# MyNixie_-_HC595.net
KiCad netlist of a schematic drawn in Altium Designer
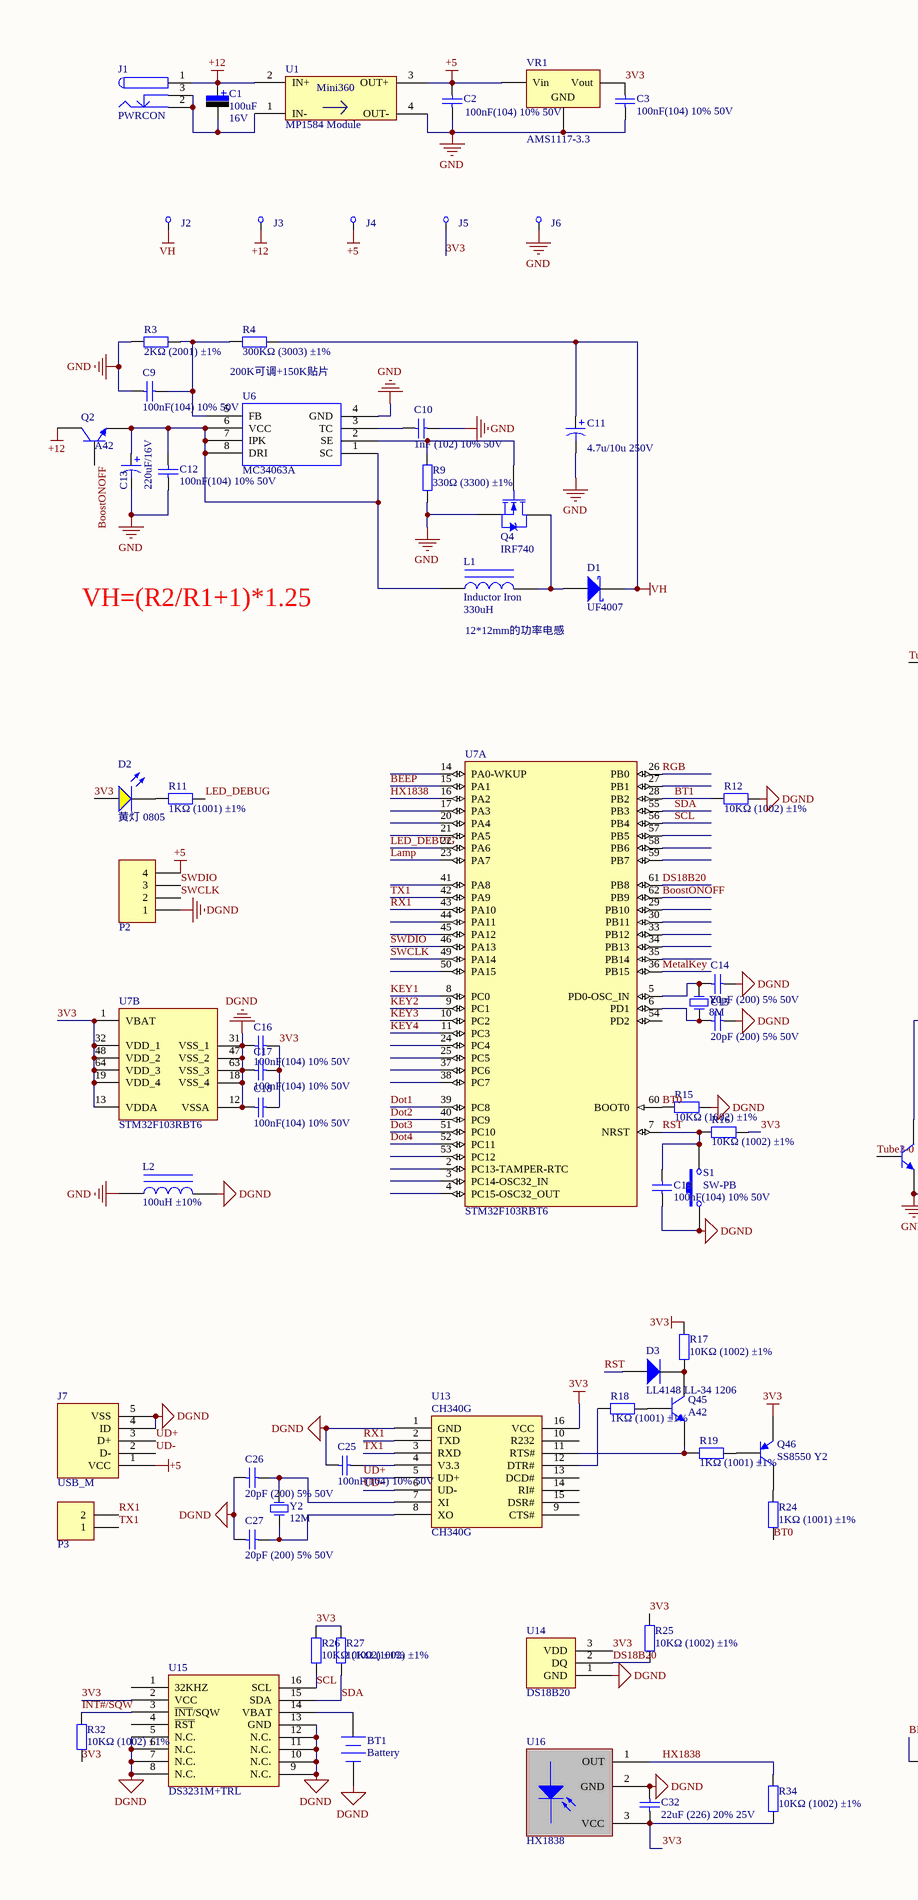
[diagram p0: MyNixie - HC595.SchDoc, left]
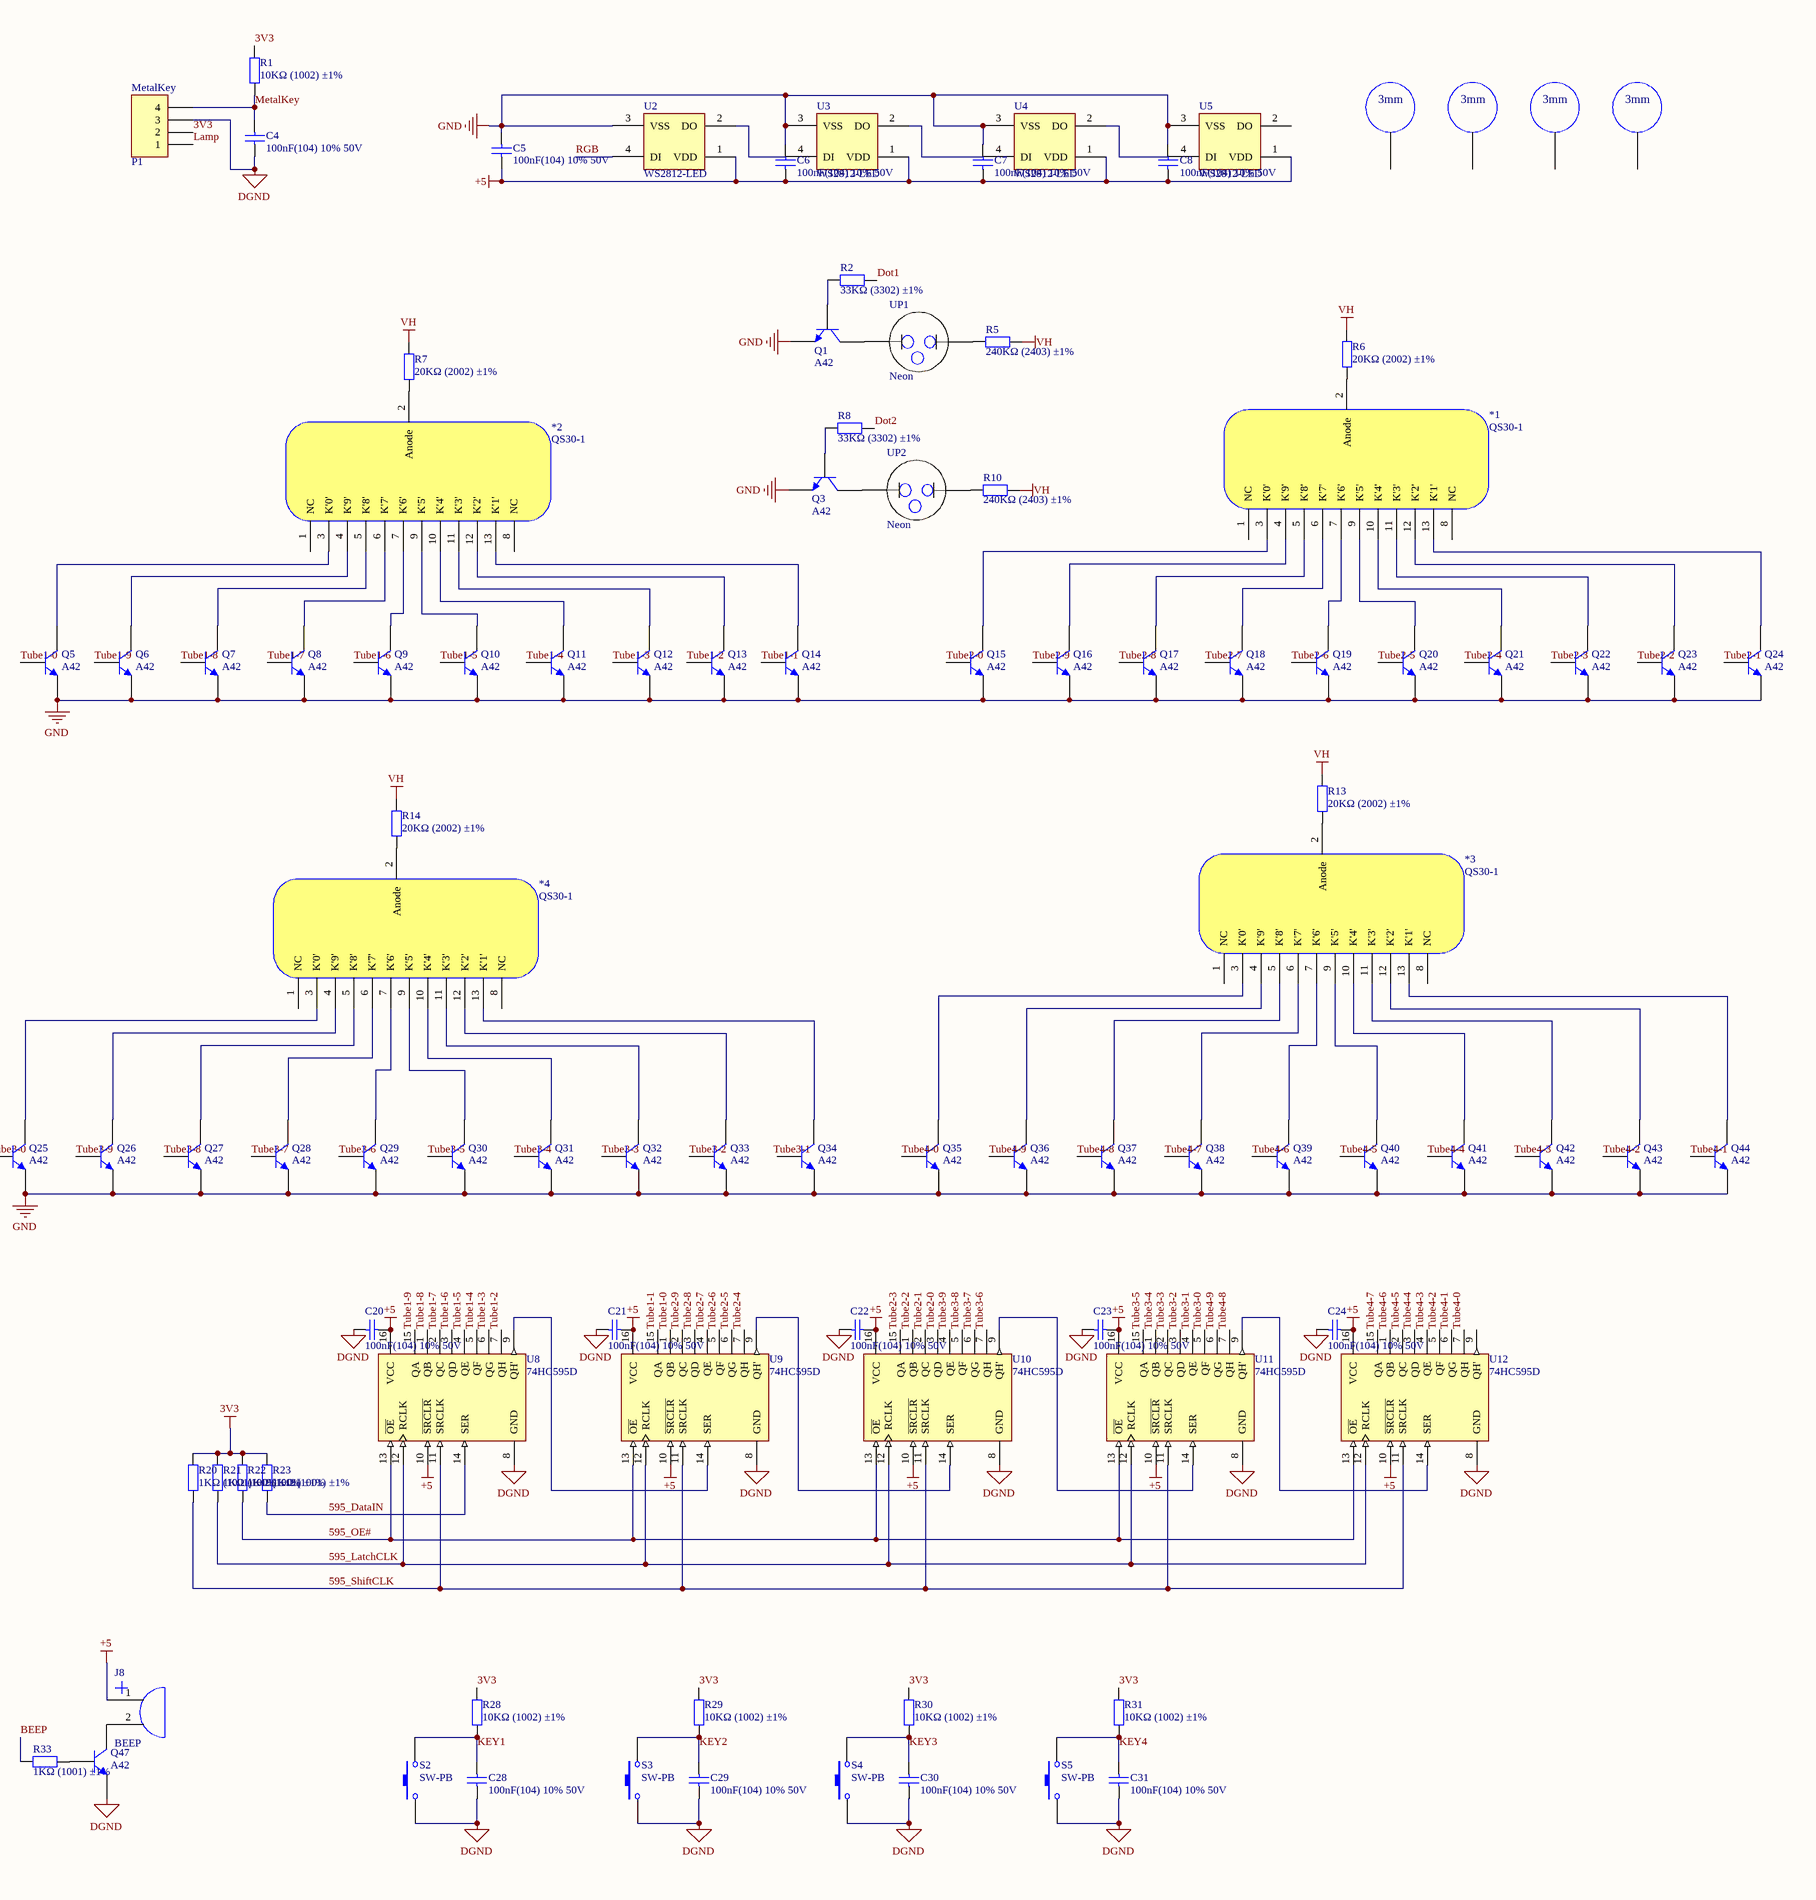
[diagram p1: MyNixie - HC595.SchDoc, right]

(export (version "E")
  (design (tool "Eeschema 10.0.6"))
  (components
    (comp (ref "*1")
      (value "QS30-1")
      (footprint "QS30-1")
      (description "南昌辉光管")
      (libsource (lib "fszhang") (part "QS30-1"))
    )
    (comp (ref "*2")
      (value "QS30-1")
      (footprint "QS30-1")
      (description "南昌辉光管")
      (libsource (lib "fszhang") (part "QS30-1"))
    )
    (comp (ref "*3")
      (value "QS30-1")
      (footprint "QS30-1")
      (description "南昌辉光管")
      (libsource (lib "fszhang") (part "QS30-1"))
    )
    (comp (ref "*4")
      (value "QS30-1")
      (footprint "QS30-1")
      (description "南昌辉光管")
      (libsource (lib "fszhang") (part "QS30-1"))
    )
    (comp (ref "BT1")
      (value "Battery")
      (footprint "CR1220")
      (description "备份电池")
      (fields (field (name "PUBLISHER") "Altium Limited"))
      (libsource (lib "fszhang") (part "Battery"))
    )
    (comp (ref "C1")
      (value "100uF")
      (footprint "C-RB-10")
      (description "极性电解电容")
      (fields
        (field (name "VOL") "16V")
        (field (name "Comment") "Cap Pol")
        (field (name "PUBLISHER") "Altium Limited")
      )
      (libsource (lib "fszhang") (part "Cap Pol"))
    )
    (comp (ref "C2")
      (value "100nF(104) 10% 50V")
      (footprint "LC-0805_C")
      (description "贴片电容")
      (libsource (lib "Miscellaneous Devices LC") (part "0805 100nF(104) 10% 50V"))
    )
    (comp (ref "C3")
      (value "100nF(104) 10% 50V")
      (footprint "LC-0805_C")
      (description "贴片电容")
      (libsource (lib "Miscellaneous Devices LC") (part "0805 100nF(104) 10% 50V"))
    )
    (comp (ref "C4")
      (value "100nF(104) 10% 50V")
      (footprint "LC-0805_C")
      (description "贴片电容")
      (libsource (lib "Miscellaneous Devices LC") (part "0805 100nF(104) 10% 50V"))
    )
    (comp (ref "C5")
      (value "100nF(104) 10% 50V")
      (footprint "LC-0805_C")
      (description "贴片电容")
      (libsource (lib "Miscellaneous Devices LC") (part "0805 100nF(104) 10% 50V"))
    )
    (comp (ref "C6")
      (value "100nF(104) 10% 50V")
      (footprint "LC-0805_C")
      (description "贴片电容")
      (libsource (lib "Miscellaneous Devices LC") (part "0805 100nF(104) 10% 50V"))
    )
    (comp (ref "C7")
      (value "100nF(104) 10% 50V")
      (footprint "LC-0805_C")
      (description "贴片电容")
      (libsource (lib "Miscellaneous Devices LC") (part "0805 100nF(104) 10% 50V"))
    )
    (comp (ref "C8")
      (value "100nF(104) 10% 50V")
      (footprint "LC-0805_C")
      (description "贴片电容")
      (libsource (lib "Miscellaneous Devices LC") (part "0805 100nF(104) 10% 50V"))
    )
    (comp (ref "C9")
      (value "100nF(104) 10% 50V")
      (footprint "LC-0805_C")
      (description "贴片电容")
      (libsource (lib "Miscellaneous Devices LC") (part "0805 100nF(104) 10% 50V"))
    )
    (comp (ref "C10")
      (value "1nF (102) 10% 50V")
      (footprint "LC-0805_C")
      (description "贴片电容")
      (libsource (lib "Miscellaneous Devices LC") (part "0805 1nF (102) 10% 50V"))
    )
    (comp (ref "C11")
      (value "4.7u/10u 250V")
      (footprint "C-RB-10")
      (description "Polarized Capacitor (Radial)")
      (fields (field (name "Comment") "Cap Pol1") (field (name "PUBLISHER") "Altium Limited"))
      (libsource (lib "Miscellaneous Devices") (part "Cap Pol1"))
    )
    (comp (ref "C12")
      (value "100nF(104) 10% 50V")
      (footprint "LC-0805_C")
      (description "贴片电容")
      (libsource (lib "Miscellaneous Devices LC") (part "0805 100nF(104) 10% 50V"))
    )
    (comp (ref "C13")
      (value "220uF/16V")
      (footprint "C-RB-6")
      (description "Polarized Capacitor (Radial)")
      (fields (field (name "Comment") "Cap Pol1") (field (name "PUBLISHER") "Altium Limited"))
      (libsource (lib "Miscellaneous Devices") (part "Cap Pol1"))
    )
    (comp (ref "C14")
      (value "20pF (200) 5% 50V")
      (footprint "LC-0805_C")
      (description "贴片电容")
      (libsource (lib "Miscellaneous Devices LC") (part "0805 20pF (200) 5% 50V"))
    )
    (comp (ref "C15")
      (value "20pF (200) 5% 50V")
      (footprint "LC-0805_C")
      (description "贴片电容")
      (libsource (lib "Miscellaneous Devices LC") (part "0805 20pF (200) 5% 50V"))
    )
    (comp (ref "C16")
      (value "100nF(104) 10% 50V")
      (footprint "LC-0805_C")
      (description "贴片电容")
      (libsource (lib "Miscellaneous Devices LC") (part "0805 100nF(104) 10% 50V"))
    )
    (comp (ref "C17")
      (value "100nF(104) 10% 50V")
      (footprint "LC-0805_C")
      (description "贴片电容")
      (libsource (lib "Miscellaneous Devices LC") (part "0805 100nF(104) 10% 50V"))
    )
    (comp (ref "C18")
      (value "100nF(104) 10% 50V")
      (footprint "LC-0805_C")
      (description "贴片电容")
      (libsource (lib "Miscellaneous Devices LC") (part "0805 100nF(104) 10% 50V"))
    )
    (comp (ref "C19")
      (value "100nF(104) 10% 50V")
      (footprint "LC-0805_C")
      (description "贴片电容")
      (libsource (lib "Miscellaneous Devices LC") (part "0805 100nF(104) 10% 50V"))
    )
    (comp (ref "C20")
      (value "100nF(104) 10% 50V")
      (footprint "LC-0805_C")
      (description "贴片电容")
      (libsource (lib "Miscellaneous Devices LC") (part "0805 100nF(104) 10% 50V"))
    )
    (comp (ref "C21")
      (value "100nF(104) 10% 50V")
      (footprint "LC-0805_C")
      (description "贴片电容")
      (libsource (lib "Miscellaneous Devices LC") (part "0805 100nF(104) 10% 50V"))
    )
    (comp (ref "C22")
      (value "100nF(104) 10% 50V")
      (footprint "LC-0805_C")
      (description "贴片电容")
      (libsource (lib "Miscellaneous Devices LC") (part "0805 100nF(104) 10% 50V"))
    )
    (comp (ref "C23")
      (value "100nF(104) 10% 50V")
      (footprint "LC-0805_C")
      (description "贴片电容")
      (libsource (lib "Miscellaneous Devices LC") (part "0805 100nF(104) 10% 50V"))
    )
    (comp (ref "C24")
      (value "100nF(104) 10% 50V")
      (footprint "LC-0805_C")
      (description "贴片电容")
      (libsource (lib "Miscellaneous Devices LC") (part "0805 100nF(104) 10% 50V"))
    )
    (comp (ref "C25")
      (value "100nF(104) 10% 50V")
      (footprint "LC-0805_C")
      (description "贴片电容")
      (libsource (lib "Miscellaneous Devices LC") (part "0805 100nF(104) 10% 50V"))
    )
    (comp (ref "C26")
      (value "20pF (200) 5% 50V")
      (footprint "LC-0805_C")
      (description "贴片电容")
      (libsource (lib "Miscellaneous Devices LC") (part "0805 20pF (200) 5% 50V"))
    )
    (comp (ref "C27")
      (value "20pF (200) 5% 50V")
      (footprint "LC-0805_C")
      (description "贴片电容")
      (libsource (lib "Miscellaneous Devices LC") (part "0805 20pF (200) 5% 50V"))
    )
    (comp (ref "C28")
      (value "100nF(104) 10% 50V")
      (footprint "LC-0805_C")
      (description "贴片电容")
      (libsource (lib "Miscellaneous Devices LC") (part "0805 100nF(104) 10% 50V"))
    )
    (comp (ref "C29")
      (value "100nF(104) 10% 50V")
      (footprint "LC-0805_C")
      (description "贴片电容")
      (libsource (lib "Miscellaneous Devices LC") (part "0805 100nF(104) 10% 50V"))
    )
    (comp (ref "C30")
      (value "100nF(104) 10% 50V")
      (footprint "LC-0805_C")
      (description "贴片电容")
      (libsource (lib "Miscellaneous Devices LC") (part "0805 100nF(104) 10% 50V"))
    )
    (comp (ref "C31")
      (value "100nF(104) 10% 50V")
      (footprint "LC-0805_C")
      (description "贴片电容")
      (libsource (lib "Miscellaneous Devices LC") (part "0805 100nF(104) 10% 50V"))
    )
    (comp (ref "C32")
      (value "22uF (226) 20% 25V")
      (footprint "LC-0805_C")
      (description "贴片电容")
      (libsource (lib "Miscellaneous Devices LC") (part "0805 22uF (226) 20% 25V"))
    )
    (comp (ref "D1")
      (value "UF4007")
      (footprint "DO-41")
      (description "Schottky Diode")
      (fields (field (name "PUBLISHER") "Altium Limited"))
      (libsource (lib "Miscellaneous Devices") (part "D Schottky"))
    )
    (comp (ref "D2")
      (value "黄灯 0805")
      (footprint "LC-0805_LED_S1")
      (description "发光二极管")
      (libsource (lib "Miscellaneous Devices LC") (part "0805 黄灯"))
    )
    (comp (ref "D3")
      (value "LL4148 LL-34 1206")
      (footprint "LC-LL-34")
      (description "开关二极管")
      (libsource (lib "Miscellaneous Devices LC") (part "LL-34 LL4148 LL-34 1206"))
    )
    (comp (ref "J1")
      (value "PWRCON")
      (footprint "DC-005")
      (description "直流电源端子")
      (fields (field (name "PUBLISHER") "Altium Limited"))
      (libsource (lib "fszhang") (part "PWRCON"))
    )
    (comp (ref "J2")
      (value "CHECK")
      (footprint "CHECK-A")
      (description "测试点")
      (libsource (lib "fszhang") (part "CHECK"))
    )
    (comp (ref "J3")
      (value "CHECK")
      (footprint "CHECK-A")
      (description "测试点")
      (libsource (lib "fszhang") (part "CHECK"))
    )
    (comp (ref "J4")
      (value "CHECK")
      (footprint "CHECK-A")
      (description "测试点")
      (libsource (lib "fszhang") (part "CHECK"))
    )
    (comp (ref "J5")
      (value "CHECK")
      (footprint "CHECK-A")
      (description "测试点")
      (libsource (lib "fszhang") (part "CHECK"))
    )
    (comp (ref "J6")
      (value "CHECK")
      (footprint "CHECK-A")
      (description "测试点")
      (libsource (lib "fszhang") (part "CHECK"))
    )
    (comp (ref "J7")
      (value "USB_M")
      (footprint "USB_MICRO")
      (description "MicroUSB接口")
      (libsource (lib "fszhang") (part "USB_M"))
    )
    (comp (ref "J8")
      (value "BEEP")
      (footprint "Beep")
      (description "蜂鸣器")
      (libsource (lib "fszhang") (part "BEEP"))
    )
    (comp (ref "L1")
      (value "Inductor Iron")
      (footprint "L-SMD-12")
      (description "Magnetic-Core Inductor")
      (fields (field (name "ALTIUM_VALUE") "330uH") (field (name "PUBLISHER") "Altium Limited"))
      (libsource (lib "Miscellaneous Devices") (part "Inductor Iron"))
    )
    (comp (ref "L2")
      (value "100uH ±10%")
      (footprint "LC-0805_L")
      (description "贴片电感")
      (libsource (lib "Miscellaneous Devices LC") (part "0805 100uH 10%"))
    )
    (comp (ref "P1")
      (value "MetalKey")
      (footprint "HDR4X1_A")
      (description "接插件")
      (fields (field (name "PUBLISHER") "Altium Limited"))
      (libsource (lib "fszhang") (part "Header 4"))
    )
    (comp (ref "P2")
      (value "Header 4")
      (footprint "HDR4X1_A")
      (description "接插件")
      (fields (field (name "PUBLISHER") "Altium Limited"))
      (libsource (lib "fszhang") (part "Header 4"))
    )
    (comp (ref "P3")
      (value "Header 2")
      (footprint "HDR2X1_A")
      (description "接插件")
      (fields (field (name "PUBLISHER") "Altium Limited"))
      (libsource (lib "fszhang") (part "Header 2"))
    )
    (comp (ref "Q1")
      (value "A42")
      (footprint "LC-SOT-23(SOT-23-3)")
      (description "三极管")
      (libsource (lib "Miscellaneous Devices LC") (part "SOT-23 SS8050 Y1"))
    )
    (comp (ref "Q2")
      (value "A42")
      (footprint "LC-SOT-23(SOT-23-3)")
      (description "三极管")
      (libsource (lib "Miscellaneous Devices LC") (part "SOT-23 SS8050 Y1"))
    )
    (comp (ref "Q3")
      (value "A42")
      (footprint "LC-SOT-23(SOT-23-3)")
      (description "三极管")
      (libsource (lib "Miscellaneous Devices LC") (part "SOT-23 SS8050 Y1"))
    )
    (comp (ref "Q4")
      (value "IRF740")
      (footprint "TO-220AB")
      (description "N-Channel Power MOSFET")
      (fields (field (name "PUBLISHER") "Altium Limited"))
      (libsource (lib "Miscellaneous Devices") (part "NMOS-2"))
    )
    (comp (ref "Q5")
      (value "A42")
      (footprint "LC-SOT-23(SOT-23-3)")
      (description "三极管")
      (libsource (lib "Miscellaneous Devices LC") (part "SOT-23 SS8050 Y1"))
    )
    (comp (ref "Q6")
      (value "A42")
      (footprint "LC-SOT-23(SOT-23-3)")
      (description "三极管")
      (libsource (lib "Miscellaneous Devices LC") (part "SOT-23 SS8050 Y1"))
    )
    (comp (ref "Q7")
      (value "A42")
      (footprint "LC-SOT-23(SOT-23-3)")
      (description "三极管")
      (libsource (lib "Miscellaneous Devices LC") (part "SOT-23 SS8050 Y1"))
    )
    (comp (ref "Q8")
      (value "A42")
      (footprint "LC-SOT-23(SOT-23-3)")
      (description "三极管")
      (libsource (lib "Miscellaneous Devices LC") (part "SOT-23 SS8050 Y1"))
    )
    (comp (ref "Q9")
      (value "A42")
      (footprint "LC-SOT-23(SOT-23-3)")
      (description "三极管")
      (libsource (lib "Miscellaneous Devices LC") (part "SOT-23 SS8050 Y1"))
    )
    (comp (ref "Q10")
      (value "A42")
      (footprint "LC-SOT-23(SOT-23-3)")
      (description "三极管")
      (libsource (lib "Miscellaneous Devices LC") (part "SOT-23 SS8050 Y1"))
    )
    (comp (ref "Q11")
      (value "A42")
      (footprint "LC-SOT-23(SOT-23-3)")
      (description "三极管")
      (libsource (lib "Miscellaneous Devices LC") (part "SOT-23 SS8050 Y1"))
    )
    (comp (ref "Q12")
      (value "A42")
      (footprint "LC-SOT-23(SOT-23-3)")
      (description "三极管")
      (libsource (lib "Miscellaneous Devices LC") (part "SOT-23 SS8050 Y1"))
    )
    (comp (ref "Q13")
      (value "A42")
      (footprint "LC-SOT-23(SOT-23-3)")
      (description "三极管")
      (libsource (lib "Miscellaneous Devices LC") (part "SOT-23 SS8050 Y1"))
    )
    (comp (ref "Q14")
      (value "A42")
      (footprint "LC-SOT-23(SOT-23-3)")
      (description "三极管")
      (libsource (lib "Miscellaneous Devices LC") (part "SOT-23 SS8050 Y1"))
    )
    (comp (ref "Q15")
      (value "A42")
      (footprint "LC-SOT-23(SOT-23-3)")
      (description "三极管")
      (libsource (lib "Miscellaneous Devices LC") (part "SOT-23 SS8050 Y1"))
    )
    (comp (ref "Q16")
      (value "A42")
      (footprint "LC-SOT-23(SOT-23-3)")
      (description "三极管")
      (libsource (lib "Miscellaneous Devices LC") (part "SOT-23 SS8050 Y1"))
    )
    (comp (ref "Q17")
      (value "A42")
      (footprint "LC-SOT-23(SOT-23-3)")
      (description "三极管")
      (libsource (lib "Miscellaneous Devices LC") (part "SOT-23 SS8050 Y1"))
    )
    (comp (ref "Q18")
      (value "A42")
      (footprint "LC-SOT-23(SOT-23-3)")
      (description "三极管")
      (libsource (lib "Miscellaneous Devices LC") (part "SOT-23 SS8050 Y1"))
    )
    (comp (ref "Q19")
      (value "A42")
      (footprint "LC-SOT-23(SOT-23-3)")
      (description "三极管")
      (libsource (lib "Miscellaneous Devices LC") (part "SOT-23 SS8050 Y1"))
    )
    (comp (ref "Q20")
      (value "A42")
      (footprint "LC-SOT-23(SOT-23-3)")
      (description "三极管")
      (libsource (lib "Miscellaneous Devices LC") (part "SOT-23 SS8050 Y1"))
    )
    (comp (ref "Q21")
      (value "A42")
      (footprint "LC-SOT-23(SOT-23-3)")
      (description "三极管")
      (libsource (lib "Miscellaneous Devices LC") (part "SOT-23 SS8050 Y1"))
    )
    (comp (ref "Q22")
      (value "A42")
      (footprint "LC-SOT-23(SOT-23-3)")
      (description "三极管")
      (libsource (lib "Miscellaneous Devices LC") (part "SOT-23 SS8050 Y1"))
    )
    (comp (ref "Q23")
      (value "A42")
      (footprint "LC-SOT-23(SOT-23-3)")
      (description "三极管")
      (libsource (lib "Miscellaneous Devices LC") (part "SOT-23 SS8050 Y1"))
    )
    (comp (ref "Q24")
      (value "A42")
      (footprint "LC-SOT-23(SOT-23-3)")
      (description "三极管")
      (libsource (lib "Miscellaneous Devices LC") (part "SOT-23 SS8050 Y1"))
    )
    (comp (ref "Q25")
      (value "A42")
      (footprint "LC-SOT-23(SOT-23-3)")
      (description "三极管")
      (libsource (lib "Miscellaneous Devices LC") (part "SOT-23 SS8050 Y1"))
    )
    (comp (ref "Q26")
      (value "A42")
      (footprint "LC-SOT-23(SOT-23-3)")
      (description "三极管")
      (libsource (lib "Miscellaneous Devices LC") (part "SOT-23 SS8050 Y1"))
    )
    (comp (ref "Q27")
      (value "A42")
      (footprint "LC-SOT-23(SOT-23-3)")
      (description "三极管")
      (libsource (lib "Miscellaneous Devices LC") (part "SOT-23 SS8050 Y1"))
    )
    (comp (ref "Q28")
      (value "A42")
      (footprint "LC-SOT-23(SOT-23-3)")
      (description "三极管")
      (libsource (lib "Miscellaneous Devices LC") (part "SOT-23 SS8050 Y1"))
    )
    (comp (ref "Q29")
      (value "A42")
      (footprint "LC-SOT-23(SOT-23-3)")
      (description "三极管")
      (libsource (lib "Miscellaneous Devices LC") (part "SOT-23 SS8050 Y1"))
    )
    (comp (ref "Q30")
      (value "A42")
      (footprint "LC-SOT-23(SOT-23-3)")
      (description "三极管")
      (libsource (lib "Miscellaneous Devices LC") (part "SOT-23 SS8050 Y1"))
    )
    (comp (ref "Q31")
      (value "A42")
      (footprint "LC-SOT-23(SOT-23-3)")
      (description "三极管")
      (libsource (lib "Miscellaneous Devices LC") (part "SOT-23 SS8050 Y1"))
    )
    (comp (ref "Q32")
      (value "A42")
      (footprint "LC-SOT-23(SOT-23-3)")
      (description "三极管")
      (libsource (lib "Miscellaneous Devices LC") (part "SOT-23 SS8050 Y1"))
    )
    (comp (ref "Q33")
      (value "A42")
      (footprint "LC-SOT-23(SOT-23-3)")
      (description "三极管")
      (libsource (lib "Miscellaneous Devices LC") (part "SOT-23 SS8050 Y1"))
    )
    (comp (ref "Q34")
      (value "A42")
      (footprint "LC-SOT-23(SOT-23-3)")
      (description "三极管")
      (libsource (lib "Miscellaneous Devices LC") (part "SOT-23 SS8050 Y1"))
    )
    (comp (ref "Q35")
      (value "A42")
      (footprint "LC-SOT-23(SOT-23-3)")
      (description "三极管")
      (libsource (lib "Miscellaneous Devices LC") (part "SOT-23 SS8050 Y1"))
    )
    (comp (ref "Q36")
      (value "A42")
      (footprint "LC-SOT-23(SOT-23-3)")
      (description "三极管")
      (libsource (lib "Miscellaneous Devices LC") (part "SOT-23 SS8050 Y1"))
    )
    (comp (ref "Q37")
      (value "A42")
      (footprint "LC-SOT-23(SOT-23-3)")
      (description "三极管")
      (libsource (lib "Miscellaneous Devices LC") (part "SOT-23 SS8050 Y1"))
    )
    (comp (ref "Q38")
      (value "A42")
      (footprint "LC-SOT-23(SOT-23-3)")
      (description "三极管")
      (libsource (lib "Miscellaneous Devices LC") (part "SOT-23 SS8050 Y1"))
    )
    (comp (ref "Q39")
      (value "A42")
      (footprint "LC-SOT-23(SOT-23-3)")
      (description "三极管")
      (libsource (lib "Miscellaneous Devices LC") (part "SOT-23 SS8050 Y1"))
    )
    (comp (ref "Q40")
      (value "A42")
      (footprint "LC-SOT-23(SOT-23-3)")
      (description "三极管")
      (libsource (lib "Miscellaneous Devices LC") (part "SOT-23 SS8050 Y1"))
    )
    (comp (ref "Q41")
      (value "A42")
      (footprint "LC-SOT-23(SOT-23-3)")
      (description "三极管")
      (libsource (lib "Miscellaneous Devices LC") (part "SOT-23 SS8050 Y1"))
    )
    (comp (ref "Q42")
      (value "A42")
      (footprint "LC-SOT-23(SOT-23-3)")
      (description "三极管")
      (libsource (lib "Miscellaneous Devices LC") (part "SOT-23 SS8050 Y1"))
    )
    (comp (ref "Q43")
      (value "A42")
      (footprint "LC-SOT-23(SOT-23-3)")
      (description "三极管")
      (libsource (lib "Miscellaneous Devices LC") (part "SOT-23 SS8050 Y1"))
    )
    (comp (ref "Q44")
      (value "A42")
      (footprint "LC-SOT-23(SOT-23-3)")
      (description "三极管")
      (libsource (lib "Miscellaneous Devices LC") (part "SOT-23 SS8050 Y1"))
    )
    (comp (ref "Q45")
      (value "A42")
      (footprint "LC-SOT-23(SOT-23-3)")
      (description "三极管")
      (libsource (lib "Miscellaneous Devices LC") (part "SOT-23 SS8050 Y1"))
    )
    (comp (ref "Q46")
      (value "SS8550 Y2")
      (footprint "LC-SOT-23(SOT-23-3)")
      (description "三极管")
      (libsource (lib "Miscellaneous Devices LC") (part "SOT-23 SS8550 Y2"))
    )
    (comp (ref "Q47")
      (value "A42")
      (footprint "LC-SOT-23(SOT-23-3)")
      (description "三极管")
      (libsource (lib "Miscellaneous Devices LC") (part "SOT-23 SS8050 Y1"))
    )
    (comp (ref "R1")
      (value "10KΩ (1002) ±1%")
      (footprint "LC-0805_R")
      (description "贴片电阻")
      (libsource (lib "") (part "0805 10KΩ (1002) 1%_2"))
    )
    (comp (ref "R2")
      (value "33KΩ (3302) ±1%")
      (footprint "LC-0805_R")
      (description "贴片电阻")
      (libsource (lib "") (part "0805 33KΩ (3302) 1%_1"))
    )
    (comp (ref "R3")
      (value "2KΩ (2001) ±1%")
      (footprint "LC-0805_R")
      (description "贴片电阻")
      (libsource (lib "Miscellaneous Devices LC") (part "0805 2KΩ (2001) 1%"))
    )
    (comp (ref "R4")
      (value "300KΩ (3003) ±1%")
      (footprint "LC-0805_R")
      (description "贴片电阻")
      (libsource (lib "Miscellaneous Devices LC") (part "0805 300KΩ (3003) 1%"))
    )
    (comp (ref "R5")
      (value "240KΩ (2403) ±1%")
      (footprint "LC-0805_R")
      (description "贴片电阻")
      (libsource (lib "Miscellaneous Devices LC") (part "0805 240KΩ (2403) 1%"))
    )
    (comp (ref "R6")
      (value "20KΩ (2002) ±1%")
      (footprint "LC-0805_R")
      (description "贴片电阻")
      (libsource (lib "Miscellaneous Devices LC") (part "0805 20KΩ (2002) 1%"))
    )
    (comp (ref "R7")
      (value "20KΩ (2002) ±1%")
      (footprint "LC-0805_R")
      (description "贴片电阻")
      (libsource (lib "Miscellaneous Devices LC") (part "0805 20KΩ (2002) 1%"))
    )
    (comp (ref "R8")
      (value "33KΩ (3302) ±1%")
      (footprint "LC-0805_R")
      (description "贴片电阻")
      (libsource (lib "Miscellaneous Devices LC") (part "0805 33KΩ (3302) 1%"))
    )
    (comp (ref "R9")
      (value "330Ω (3300) ±1%")
      (footprint "LC-0805_R")
      (description "贴片电阻")
      (libsource (lib "Miscellaneous Devices LC") (part "0805 330Ω (3300) 1%"))
    )
    (comp (ref "R10")
      (value "240KΩ (2403) ±1%")
      (footprint "LC-0805_R")
      (description "贴片电阻")
      (libsource (lib "Miscellaneous Devices LC") (part "0805 240KΩ (2403) 1%"))
    )
    (comp (ref "R11")
      (value "1KΩ (1001) ±1%")
      (footprint "LC-0805_R")
      (description "贴片电阻")
      (libsource (lib "") (part "0805 1KΩ (1001) 1%_1"))
    )
    (comp (ref "R12")
      (value "10KΩ (1002) ±1%")
      (footprint "LC-0805_R")
      (description "贴片电阻")
      (libsource (lib "Miscellaneous Devices LC") (part "0805 10KΩ (1002) 1%"))
    )
    (comp (ref "R13")
      (value "20KΩ (2002) ±1%")
      (footprint "LC-0805_R")
      (description "贴片电阻")
      (libsource (lib "Miscellaneous Devices LC") (part "0805 20KΩ (2002) 1%"))
    )
    (comp (ref "R14")
      (value "20KΩ (2002) ±1%")
      (footprint "LC-0805_R")
      (description "贴片电阻")
      (libsource (lib "Miscellaneous Devices LC") (part "0805 20KΩ (2002) 1%"))
    )
    (comp (ref "R15")
      (value "10KΩ (1002) ±1%")
      (footprint "LC-0805_R")
      (description "贴片电阻")
      (libsource (lib "Miscellaneous Devices LC") (part "0805 10KΩ (1002) 1%"))
    )
    (comp (ref "R16")
      (value "10KΩ (1002) ±1%")
      (footprint "LC-0805_R")
      (description "贴片电阻")
      (libsource (lib "Miscellaneous Devices LC") (part "0805 10KΩ (1002) 1%"))
    )
    (comp (ref "R17")
      (value "10KΩ (1002) ±1%")
      (footprint "LC-0805_R")
      (description "贴片电阻")
      (libsource (lib "") (part "0805 10KΩ (1002) 1%_1"))
    )
    (comp (ref "R18")
      (value "1KΩ (1001) ±1%")
      (footprint "LC-0805_R")
      (description "贴片电阻")
      (libsource (lib "") (part "0805 1KΩ (1001) 1%_1"))
    )
    (comp (ref "R19")
      (value "1KΩ (1001) ±1%")
      (footprint "LC-0805_R")
      (description "贴片电阻")
      (libsource (lib "") (part "0805 1KΩ (1001) 1%_1"))
    )
    (comp (ref "R20")
      (value "1KΩ (1001) ±1%")
      (footprint "LC-0805_R")
      (description "贴片电阻")
      (libsource (lib "Miscellaneous Devices LC") (part "0805 1KΩ (1001) 1%"))
    )
    (comp (ref "R21")
      (value "1KΩ (1001) ±1%")
      (footprint "LC-0805_R")
      (description "贴片电阻")
      (libsource (lib "Miscellaneous Devices LC") (part "0805 1KΩ (1001) 1%"))
    )
    (comp (ref "R22")
      (value "1KΩ (1001) ±1%")
      (footprint "LC-0805_R")
      (description "贴片电阻")
      (libsource (lib "Miscellaneous Devices LC") (part "0805 1KΩ (1001) 1%"))
    )
    (comp (ref "R23")
      (value "1KΩ (1001) ±1%")
      (footprint "LC-0805_R")
      (description "贴片电阻")
      (libsource (lib "Miscellaneous Devices LC") (part "0805 1KΩ (1001) 1%"))
    )
    (comp (ref "R24")
      (value "1KΩ (1001) ±1%")
      (footprint "LC-0805_R")
      (description "贴片电阻")
      (libsource (lib "Miscellaneous Devices LC") (part "0805 1KΩ (1001) 1%"))
    )
    (comp (ref "R25")
      (value "10KΩ (1002) ±1%")
      (footprint "LC-0805_R")
      (description "贴片电阻")
      (libsource (lib "Miscellaneous Devices LC") (part "0805 10KΩ (1002) 1%"))
    )
    (comp (ref "R26")
      (value "10KΩ (1002) ±1%")
      (footprint "LC-0805_R")
      (description "贴片电阻")
      (libsource (lib "Miscellaneous Devices LC") (part "0805 10KΩ (1002) 1%"))
    )
    (comp (ref "R27")
      (value "10KΩ (1002) ±1%")
      (footprint "LC-0805_R")
      (description "贴片电阻")
      (libsource (lib "Miscellaneous Devices LC") (part "0805 10KΩ (1002) 1%"))
    )
    (comp (ref "R28")
      (value "10KΩ (1002) ±1%")
      (footprint "LC-0805_R")
      (description "贴片电阻")
      (libsource (lib "") (part "0805 10KΩ (1002) 1%_2"))
    )
    (comp (ref "R29")
      (value "10KΩ (1002) ±1%")
      (footprint "LC-0805_R")
      (description "贴片电阻")
      (libsource (lib "") (part "0805 10KΩ (1002) 1%_2"))
    )
    (comp (ref "R30")
      (value "10KΩ (1002) ±1%")
      (footprint "LC-0805_R")
      (description "贴片电阻")
      (libsource (lib "") (part "0805 10KΩ (1002) 1%_2"))
    )
    (comp (ref "R31")
      (value "10KΩ (1002) ±1%")
      (footprint "LC-0805_R")
      (description "贴片电阻")
      (libsource (lib "") (part "0805 10KΩ (1002) 1%_2"))
    )
    (comp (ref "R32")
      (value "10KΩ (1002) ±1%")
      (footprint "LC-0805_R")
      (description "贴片电阻")
      (libsource (lib "Miscellaneous Devices LC") (part "0805 10KΩ (1002) 1%"))
    )
    (comp (ref "R33")
      (value "1KΩ (1001) ±1%")
      (footprint "LC-0805_R")
      (description "贴片电阻")
      (libsource (lib "") (part "0805 1KΩ (1001) 1%_1"))
    )
    (comp (ref "R34")
      (value "10KΩ (1002) ±1%")
      (footprint "LC-0805_R")
      (description "贴片电阻")
      (libsource (lib "Miscellaneous Devices LC") (part "0805 10KΩ (1002) 1%"))
    )
    (comp (ref "S1")
      (value "SW-PB")
      (footprint "SW_PB2_A1")
      (description "微动开关")
      (fields (field (name "PUBLISHER") "Altium Limited"))
      (libsource (lib "fszhang") (part "SW-PB"))
    )
    (comp (ref "S2")
      (value "SW-PB")
      (footprint "SW_PB2_A1")
      (description "微动开关")
      (fields (field (name "PUBLISHER") "Altium Limited"))
      (libsource (lib "fszhang") (part "SW-PB"))
    )
    (comp (ref "S3")
      (value "SW-PB")
      (footprint "SW_PB2_A1")
      (description "微动开关")
      (fields (field (name "PUBLISHER") "Altium Limited"))
      (libsource (lib "fszhang") (part "SW-PB"))
    )
    (comp (ref "S4")
      (value "SW-PB")
      (footprint "SW_PB2_A1")
      (description "微动开关")
      (fields (field (name "PUBLISHER") "Altium Limited"))
      (libsource (lib "fszhang") (part "SW-PB"))
    )
    (comp (ref "S5")
      (value "SW-PB")
      (footprint "SW_PB2_A1")
      (description "微动开关")
      (fields (field (name "PUBLISHER") "Altium Limited"))
      (libsource (lib "fszhang") (part "SW-PB"))
    )
    (comp (ref "T1") (value "M3铜柱螺丝孔") (footprint "螺丝孔-3mm") (libsource (lib "fszhang") (part "M3铜柱螺丝孔")))
    (comp (ref "T2") (value "M3铜柱螺丝孔") (footprint "螺丝孔-3mm") (libsource (lib "fszhang") (part "M3铜柱螺丝孔")))
    (comp (ref "T3") (value "M3铜柱螺丝孔") (footprint "螺丝孔-3mm") (libsource (lib "fszhang") (part "M3铜柱螺丝孔")))
    (comp (ref "T4") (value "M3铜柱螺丝孔") (footprint "螺丝孔-3mm") (libsource (lib "fszhang") (part "M3铜柱螺丝孔")))
    (comp (ref "U1")
      (value "MP1584 Module")
      (footprint "MP1584 Module")
      (libsource (lib "fszhang") (part "MP1584 Module"))
    )
    (comp (ref "U2")
      (value "WS2812-LED")
      (footprint "WS2812")
      (libsource (lib "fszhang") (part "WS2812-LED"))
    )
    (comp (ref "U3")
      (value "WS2812-LED")
      (footprint "WS2812")
      (libsource (lib "fszhang") (part "WS2812-LED"))
    )
    (comp (ref "U4")
      (value "WS2812-LED")
      (footprint "WS2812")
      (libsource (lib "fszhang") (part "WS2812-LED"))
    )
    (comp (ref "U5")
      (value "WS2812-LED")
      (footprint "WS2812")
      (libsource (lib "fszhang") (part "WS2812-LED"))
    )
    (comp (ref "U6")
      (value "MC34063A")
      (footprint "LC-SOIC-8_150mil")
      (libsource (lib "NIXIEClock_SCHLib") (part "MC34063A"))
    )
    (comp (ref "U7")
      (value "STM32F103RBT6")
      (footprint "LC-LQFP-64_10x10x05P")
      (description "ARM")
      (libsource (lib "Miscellaneous Devices LC") (part "STM32F103RBT6"))
    )
    (comp (ref "U8")
      (value "74HC595D")
      (footprint "LC-SOIC-16_150mil")
      (description "74系列逻辑芯片")
      (libsource (lib "Miscellaneous Devices LC") (part "74HC595D"))
    )
    (comp (ref "U9")
      (value "74HC595D")
      (footprint "LC-SOIC-16_150mil")
      (description "74系列逻辑芯片")
      (libsource (lib "Miscellaneous Devices LC") (part "74HC595D"))
    )
    (comp (ref "U10")
      (value "74HC595D")
      (footprint "LC-SOIC-16_150mil")
      (description "74系列逻辑芯片")
      (libsource (lib "Miscellaneous Devices LC") (part "74HC595D"))
    )
    (comp (ref "U11")
      (value "74HC595D")
      (footprint "LC-SOIC-16_150mil")
      (description "74系列逻辑芯片")
      (libsource (lib "Miscellaneous Devices LC") (part "74HC595D"))
    )
    (comp (ref "U12")
      (value "74HC595D")
      (footprint "LC-SOIC-16_150mil")
      (description "74系列逻辑芯片")
      (libsource (lib "Miscellaneous Devices LC") (part "74HC595D"))
    )
    (comp (ref "U13")
      (value "CH340G")
      (footprint "LC-SOIC-16_150mil")
      (description "USB")
      (libsource (lib "Miscellaneous Devices LC") (part "CH340G"))
    )
    (comp (ref "U14")
      (value "DS18B20")
      (footprint "TO-92A")
      (description "温度传感器")
      (libsource (lib "fszhang") (part "DS18B20"))
    )
    (comp (ref "U15")
      (value "DS3231M+TRL")
      (footprint "LC-SOIC-16_300mil")
      (description "实时时钟")
      (libsource (lib "Miscellaneous Devices LC") (part "DS3231M+TRL"))
    )
    (comp (ref "U16")
      (value "HX1838")
      (footprint "HS0038B")
      (description "红外接收器")
      (libsource (lib "fszhang") (part "HS0038B"))
    )
    (comp (ref "UP1") (value "Neon") (description "氖泡") (libsource (lib "fszhang") (part "Neon")))
    (comp (ref "UP2") (value "Neon") (description "氖泡") (libsource (lib "fszhang") (part "Neon")))
    (comp (ref "VR1")
      (value "AMS1117-3.3")
      (footprint "LC-SOT-223")
      (description "低压差线性稳压(LDO)")
      (libsource (lib "Miscellaneous Devices LC") (part "SOT-223 AMS1117-3.3"))
    )
    (comp (ref "Y1")
      (value "8M")
      (footprint "X-HC49U")
      (description "晶振")
      (fields (field (name "Comment") "XTAL") (field (name "PUBLISHER") "Altium Limited"))
      (libsource (lib "fszhang") (part "XTAL"))
    )
    (comp (ref "Y2")
      (value "12M")
      (footprint "X-HC49U")
      (description "晶振")
      (fields (field (name "Comment") "XTAL") (field (name "PUBLISHER") "Altium Limited"))
      (libsource (lib "fszhang") (part "XTAL"))
    )
  )
  (nets
    (net (code "1") (name "+5") (class "Default")
      (node (ref "C2") (pin "2") (pinfunction "2_2") (pintype "passive"))
      (node (ref "C20") (pin "1") (pinfunction "1_1") (pintype "passive"))
      (node (ref "C21") (pin "1") (pinfunction "1_1") (pintype "passive"))
      (node (ref "C22") (pin "1") (pinfunction "1_1") (pintype "passive"))
      (node (ref "C23") (pin "1") (pinfunction "1_1") (pintype "passive"))
      (node (ref "C24") (pin "1") (pinfunction "1_1") (pintype "passive"))
      (node (ref "C5") (pin "1") (pinfunction "1_1") (pintype "passive"))
      (node (ref "C6") (pin "1") (pinfunction "1_1") (pintype "passive"))
      (node (ref "C7") (pin "1") (pinfunction "1_1") (pintype "passive"))
      (node (ref "C8") (pin "1") (pinfunction "1_1") (pintype "passive"))
      (node (ref "J4") (pin "1") (pinfunction "1_1") (pintype "passive"))
      (node (ref "J7") (pin "1") (pinfunction "VCC_1") (pintype "passive"))
      (node (ref "J8") (pin "1") (pinfunction "0_1") (pintype "passive"))
      (node (ref "P2") (pin "4") (pinfunction "4_4") (pintype "passive"))
      (node (ref "U1") (pin "3") (pinfunction "OUT+_3") (pintype "passive"))
      (node (ref "U10") (pin "10") (pinfunction "~{SRCLR}_10") (pintype "input"))
      (node (ref "U10") (pin "16") (pinfunction "VCC_16") (pintype "power_in"))
      (node (ref "U11") (pin "10") (pinfunction "~{SRCLR}_10") (pintype "input"))
      (node (ref "U11") (pin "16") (pinfunction "VCC_16") (pintype "power_in"))
      (node (ref "U12") (pin "10") (pinfunction "~{SRCLR}_10") (pintype "input"))
      (node (ref "U12") (pin "16") (pinfunction "VCC_16") (pintype "power_in"))
      (node (ref "U2") (pin "1") (pinfunction "VDD_1") (pintype "passive"))
      (node (ref "U3") (pin "1") (pinfunction "VDD_1") (pintype "passive"))
      (node (ref "U4") (pin "1") (pinfunction "VDD_1") (pintype "passive"))
      (node (ref "U5") (pin "1") (pinfunction "VDD_1") (pintype "passive"))
      (node (ref "U8") (pin "10") (pinfunction "~{SRCLR}_10") (pintype "input"))
      (node (ref "U8") (pin "16") (pinfunction "VCC_16") (pintype "power_in"))
      (node (ref "U9") (pin "10") (pinfunction "~{SRCLR}_10") (pintype "input"))
      (node (ref "U9") (pin "16") (pinfunction "VCC_16") (pintype "power_in"))
      (node (ref "VR1") (pin "3") (pinfunction "Vin_3") (pintype "passive"))
    )
    (net (code "2") (name "+12") (class "Default")
      (node (ref "C1") (pin "1") (pinfunction "1_1") (pintype "passive"))
      (node (ref "J1") (pin "1") (pinfunction "1_1") (pintype "power_in"))
      (node (ref "J3") (pin "1") (pinfunction "1_1") (pintype "passive"))
      (node (ref "Q2") (pin "3") (pinfunction "C_3") (pintype "passive"))
      (node (ref "U1") (pin "2") (pinfunction "IN+_2") (pintype "passive"))
    )
    (net (code "3") (name "/595_DataIN") (class "Default")
      (node (ref "R23") (pin "1") (pinfunction "1_1") (pintype "passive"))
      (node (ref "U8") (pin "14") (pinfunction "SER_14") (pintype "input"))
    )
    (net (code "4") (name "/595_LatchCLK") (class "Default")
      (node (ref "R21") (pin "1") (pinfunction "1_1") (pintype "passive"))
      (node (ref "U10") (pin "12") (pinfunction "RCLK_12") (pintype "input"))
      (node (ref "U11") (pin "12") (pinfunction "RCLK_12") (pintype "input"))
      (node (ref "U12") (pin "12") (pinfunction "RCLK_12") (pintype "input"))
      (node (ref "U8") (pin "12") (pinfunction "RCLK_12") (pintype "input"))
      (node (ref "U9") (pin "12") (pinfunction "RCLK_12") (pintype "input"))
    )
    (net (code "5") (name "/595_OE#") (class "Default")
      (node (ref "R22") (pin "1") (pinfunction "1_1") (pintype "passive"))
      (node (ref "U10") (pin "13") (pinfunction "~{OE}_13") (pintype "input"))
      (node (ref "U11") (pin "13") (pinfunction "~{OE}_13") (pintype "input"))
      (node (ref "U12") (pin "13") (pinfunction "~{OE}_13") (pintype "input"))
      (node (ref "U8") (pin "13") (pinfunction "~{OE}_13") (pintype "input"))
      (node (ref "U9") (pin "13") (pinfunction "~{OE}_13") (pintype "input"))
    )
    (net (code "6") (name "/595_ShiftCLK") (class "Default")
      (node (ref "R20") (pin "1") (pinfunction "1_1") (pintype "passive"))
      (node (ref "U10") (pin "11") (pinfunction "SRCLK_11") (pintype "input"))
      (node (ref "U11") (pin "11") (pinfunction "SRCLK_11") (pintype "input"))
      (node (ref "U12") (pin "11") (pinfunction "SRCLK_11") (pintype "input"))
      (node (ref "U8") (pin "11") (pinfunction "SRCLK_11") (pintype "input"))
      (node (ref "U9") (pin "11") (pinfunction "SRCLK_11") (pintype "input"))
    )
    (net (code "7") (name "/BEEP") (class "Default")
      (node (ref "R33") (pin "1") (pinfunction "1_1") (pintype "passive"))
      (node (ref "U7") (pin "15") (pinfunction "PA1_15") (pintype "bidirectional"))
    )
    (net (code "8") (name "/BT0") (class "Default")
      (node (ref "R15") (pin "2") (pinfunction "2_2") (pintype "passive"))
      (node (ref "R24") (pin "1") (pinfunction "1_1") (pintype "passive"))
      (node (ref "U7") (pin "60") (pinfunction "BOOT0_60") (pintype "input"))
    )
    (net (code "9") (name "/BT1") (class "Default")
      (node (ref "R12") (pin "2") (pinfunction "2_2") (pintype "passive"))
      (node (ref "U7") (pin "28") (pinfunction "PB2_28") (pintype "bidirectional"))
    )
    (net (code "10") (name "/BoostONOFF") (class "Default")
      (node (ref "Q2") (pin "1") (pinfunction "B_1") (pintype "passive"))
      (node (ref "U7") (pin "62") (pinfunction "PB9_62") (pintype "bidirectional"))
    )
    (net (code "11") (name "/DS18B20") (class "Default")
      (node (ref "R25") (pin "2") (pinfunction "2_2") (pintype "passive"))
      (node (ref "U14") (pin "2") (pinfunction "DQ_2") (pintype "passive"))
      (node (ref "U7") (pin "61") (pinfunction "PB8_61") (pintype "bidirectional"))
    )
    (net (code "12") (name "/Dot1") (class "Default")
      (node (ref "R2") (pin "1") (pinfunction "1_1") (pintype "passive"))
      (node (ref "U7") (pin "39") (pinfunction "PC8_39") (pintype "bidirectional"))
    )
    (net (code "13") (name "/Dot2") (class "Default")
      (node (ref "R8") (pin "2") (pinfunction "2_2") (pintype "passive"))
      (node (ref "U7") (pin "40") (pinfunction "PC9_40") (pintype "bidirectional"))
    )
    (net (code "14") (name "/Dot3") (class "Default")
      (node (ref "U7") (pin "51") (pinfunction "PC10_51") (pintype "bidirectional"))
    )
    (net (code "15") (name "/Dot4") (class "Default")
      (node (ref "U7") (pin "52") (pinfunction "PC11_52") (pintype "bidirectional"))
    )
    (net (code "16") (name "/HX1838") (class "Default")
      (node (ref "R34") (pin "1") (pinfunction "1_1") (pintype "passive"))
      (node (ref "U16") (pin "1") (pinfunction "OUT_1") (pintype "passive"))
      (node (ref "U7") (pin "16") (pinfunction "PA2_16") (pintype "bidirectional"))
    )
    (net (code "17") (name "/INT#{slash}SQW") (class "Default")
      (node (ref "R32") (pin "1") (pinfunction "1_1") (pintype "passive"))
      (node (ref "U15") (pin "3") (pinfunction "~{INT}/SQW_3") (pintype "passive"))
    )
    (net (code "18") (name "/KEY1") (class "Default")
      (node (ref "C28") (pin "2") (pinfunction "2_2") (pintype "passive"))
      (node (ref "R28") (pin "2") (pinfunction "2_2") (pintype "passive"))
      (node (ref "S2") (pin "2") (pinfunction "2_2") (pintype "passive"))
      (node (ref "U7") (pin "8") (pinfunction "PC0_8") (pintype "bidirectional"))
    )
    (net (code "19") (name "/KEY2") (class "Default")
      (node (ref "C29") (pin "2") (pinfunction "2_2") (pintype "passive"))
      (node (ref "R29") (pin "2") (pinfunction "2_2") (pintype "passive"))
      (node (ref "S3") (pin "2") (pinfunction "2_2") (pintype "passive"))
      (node (ref "U7") (pin "9") (pinfunction "PC1_9") (pintype "bidirectional"))
    )
    (net (code "20") (name "/KEY3") (class "Default")
      (node (ref "C30") (pin "2") (pinfunction "2_2") (pintype "passive"))
      (node (ref "R30") (pin "2") (pinfunction "2_2") (pintype "passive"))
      (node (ref "S4") (pin "2") (pinfunction "2_2") (pintype "passive"))
      (node (ref "U7") (pin "10") (pinfunction "PC2_10") (pintype "bidirectional"))
    )
    (net (code "21") (name "/KEY4") (class "Default")
      (node (ref "C31") (pin "2") (pinfunction "2_2") (pintype "passive"))
      (node (ref "R31") (pin "2") (pinfunction "2_2") (pintype "passive"))
      (node (ref "S5") (pin "2") (pinfunction "2_2") (pintype "passive"))
      (node (ref "U7") (pin "11") (pinfunction "PC3_11") (pintype "bidirectional"))
    )
    (net (code "22") (name "/LED_DEBUG") (class "Default")
      (node (ref "R11") (pin "2") (pinfunction "2_2") (pintype "passive"))
      (node (ref "U7") (pin "22") (pinfunction "PA6_22") (pintype "bidirectional"))
    )
    (net (code "23") (name "/Lamp") (class "Default")
      (node (ref "P1") (pin "1") (pinfunction "1_1") (pintype "passive"))
      (node (ref "U7") (pin "23") (pinfunction "PA7_23") (pintype "bidirectional"))
    )
    (net (code "24") (name "/MetalKey") (class "Default")
      (node (ref "C4") (pin "2") (pinfunction "2_2") (pintype "passive"))
      (node (ref "P1") (pin "4") (pinfunction "4_4") (pintype "passive"))
      (node (ref "R1") (pin "2") (pinfunction "2_2") (pintype "passive"))
      (node (ref "U7") (pin "36") (pinfunction "PB15_36") (pintype "bidirectional"))
    )
    (net (code "25") (name "/RGB") (class "Default")
      (node (ref "U2") (pin "4") (pinfunction "DI_4") (pintype "passive"))
      (node (ref "U7") (pin "26") (pinfunction "PB0_26") (pintype "bidirectional"))
    )
    (net (code "26") (name "/RST") (class "Default")
      (node (ref "C19") (pin "2") (pinfunction "2_2") (pintype "passive"))
      (node (ref "D3") (pin "1") (pinfunction "A_1") (pintype "passive"))
      (node (ref "R16") (pin "2") (pinfunction "2_2") (pintype "passive"))
      (node (ref "S1") (pin "1") (pinfunction "1_1") (pintype "passive"))
      (node (ref "U7") (pin "7") (pinfunction "NRST_7") (pintype "bidirectional"))
    )
    (net (code "27") (name "/RX1") (class "Default")
      (node (ref "P3") (pin "2") (pinfunction "2_2") (pintype "passive"))
      (node (ref "U13") (pin "2") (pinfunction "TXD_2") (pintype "passive"))
      (node (ref "U7") (pin "43") (pinfunction "PA10_43") (pintype "bidirectional"))
    )
    (net (code "28") (name "/SCL") (class "Default")
      (node (ref "R26") (pin "2") (pinfunction "2_2") (pintype "passive"))
      (node (ref "U15") (pin "16") (pinfunction "SCL_16") (pintype "passive"))
      (node (ref "U7") (pin "56") (pinfunction "PB4_56") (pintype "bidirectional"))
    )
    (net (code "29") (name "/SDA") (class "Default")
      (node (ref "R27") (pin "2") (pinfunction "2_2") (pintype "passive"))
      (node (ref "U15") (pin "15") (pinfunction "SDA_15") (pintype "passive"))
      (node (ref "U7") (pin "55") (pinfunction "PB3_55") (pintype "bidirectional"))
    )
    (net (code "30") (name "/SWCLK") (class "Default")
      (node (ref "P2") (pin "2") (pinfunction "2_2") (pintype "passive"))
      (node (ref "U7") (pin "49") (pinfunction "PA14_49") (pintype "bidirectional"))
    )
    (net (code "31") (name "/SWDIO") (class "Default")
      (node (ref "P2") (pin "3") (pinfunction "3_3") (pintype "passive"))
      (node (ref "U7") (pin "46") (pinfunction "PA13_46") (pintype "bidirectional"))
    )
    (net (code "32") (name "/TX1") (class "Default")
      (node (ref "P3") (pin "1") (pinfunction "1_1") (pintype "passive"))
      (node (ref "U13") (pin "3") (pinfunction "RXD_3") (pintype "passive"))
      (node (ref "U7") (pin "42") (pinfunction "PA9_42") (pintype "bidirectional"))
    )
    (net (code "33") (name "/Tube1-0") (class "Default")
      (node (ref "Q5") (pin "1") (pinfunction "B_1") (pintype "passive"))
      (node (ref "U9") (pin "1") (pinfunction "QB_1") (pintype "tri_state"))
    )
    (net (code "34") (name "/Tube1-1") (class "Default")
      (node (ref "Q14") (pin "1") (pinfunction "B_1") (pintype "passive"))
      (node (ref "U9") (pin "15") (pinfunction "QA_15") (pintype "tri_state"))
    )
    (net (code "35") (name "/Tube1-2") (class "Default")
      (node (ref "Q13") (pin "1") (pinfunction "B_1") (pintype "passive"))
      (node (ref "U8") (pin "7") (pinfunction "QH_7") (pintype "tri_state"))
    )
    (net (code "36") (name "/Tube1-3") (class "Default")
      (node (ref "Q12") (pin "1") (pinfunction "B_1") (pintype "passive"))
      (node (ref "U8") (pin "6") (pinfunction "QG_6") (pintype "tri_state"))
    )
    (net (code "37") (name "/Tube1-4") (class "Default")
      (node (ref "Q11") (pin "1") (pinfunction "B_1") (pintype "passive"))
      (node (ref "U8") (pin "5") (pinfunction "QF_5") (pintype "tri_state"))
    )
    (net (code "38") (name "/Tube1-5") (class "Default")
      (node (ref "Q10") (pin "1") (pinfunction "B_1") (pintype "passive"))
      (node (ref "U8") (pin "4") (pinfunction "QE_4") (pintype "tri_state"))
    )
    (net (code "39") (name "/Tube1-6") (class "Default")
      (node (ref "Q9") (pin "1") (pinfunction "B_1") (pintype "passive"))
      (node (ref "U8") (pin "3") (pinfunction "QD_3") (pintype "tri_state"))
    )
    (net (code "40") (name "/Tube1-7") (class "Default")
      (node (ref "Q8") (pin "1") (pinfunction "B_1") (pintype "passive"))
      (node (ref "U8") (pin "2") (pinfunction "QC_2") (pintype "tri_state"))
    )
    (net (code "41") (name "/Tube1-8") (class "Default")
      (node (ref "Q7") (pin "1") (pinfunction "B_1") (pintype "passive"))
      (node (ref "U8") (pin "1") (pinfunction "QB_1") (pintype "tri_state"))
    )
    (net (code "42") (name "/Tube1-9") (class "Default")
      (node (ref "Q6") (pin "1") (pinfunction "B_1") (pintype "passive"))
      (node (ref "U8") (pin "15") (pinfunction "QA_15") (pintype "tri_state"))
    )
    (net (code "43") (name "/Tube2-0") (class "Default")
      (node (ref "Q15") (pin "1") (pinfunction "B_1") (pintype "passive"))
      (node (ref "U10") (pin "3") (pinfunction "QD_3") (pintype "tri_state"))
    )
    (net (code "44") (name "/Tube2-1") (class "Default")
      (node (ref "Q24") (pin "1") (pinfunction "B_1") (pintype "passive"))
      (node (ref "U10") (pin "2") (pinfunction "QC_2") (pintype "tri_state"))
    )
    (net (code "45") (name "/Tube2-2") (class "Default")
      (node (ref "Q23") (pin "1") (pinfunction "B_1") (pintype "passive"))
      (node (ref "U10") (pin "1") (pinfunction "QB_1") (pintype "tri_state"))
    )
    (net (code "46") (name "/Tube2-3") (class "Default")
      (node (ref "Q22") (pin "1") (pinfunction "B_1") (pintype "passive"))
      (node (ref "U10") (pin "15") (pinfunction "QA_15") (pintype "tri_state"))
    )
    (net (code "47") (name "/Tube2-4") (class "Default")
      (node (ref "Q21") (pin "1") (pinfunction "B_1") (pintype "passive"))
      (node (ref "U9") (pin "7") (pinfunction "QH_7") (pintype "tri_state"))
    )
    (net (code "48") (name "/Tube2-5") (class "Default")
      (node (ref "Q20") (pin "1") (pinfunction "B_1") (pintype "passive"))
      (node (ref "U9") (pin "6") (pinfunction "QG_6") (pintype "tri_state"))
    )
    (net (code "49") (name "/Tube2-6") (class "Default")
      (node (ref "Q19") (pin "1") (pinfunction "B_1") (pintype "passive"))
      (node (ref "U9") (pin "5") (pinfunction "QF_5") (pintype "tri_state"))
    )
    (net (code "50") (name "/Tube2-7") (class "Default")
      (node (ref "Q18") (pin "1") (pinfunction "B_1") (pintype "passive"))
      (node (ref "U9") (pin "4") (pinfunction "QE_4") (pintype "tri_state"))
    )
    (net (code "51") (name "/Tube2-8") (class "Default")
      (node (ref "Q17") (pin "1") (pinfunction "B_1") (pintype "passive"))
      (node (ref "U9") (pin "3") (pinfunction "QD_3") (pintype "tri_state"))
    )
    (net (code "52") (name "/Tube2-9") (class "Default")
      (node (ref "Q16") (pin "1") (pinfunction "B_1") (pintype "passive"))
      (node (ref "U9") (pin "2") (pinfunction "QC_2") (pintype "tri_state"))
    )
    (net (code "53") (name "/Tube3-0") (class "Default")
      (node (ref "Q25") (pin "1") (pinfunction "B_1") (pintype "passive"))
      (node (ref "U11") (pin "5") (pinfunction "QF_5") (pintype "tri_state"))
    )
    (net (code "54") (name "/Tube3-1") (class "Default")
      (node (ref "U11") (pin "4") (pinfunction "QE_4") (pintype "tri_state"))
    )
    (net (code "55") (name "/Tube3-2") (class "Default")
      (node (ref "Q33") (pin "1") (pinfunction "B_1") (pintype "passive"))
      (node (ref "U11") (pin "3") (pinfunction "QD_3") (pintype "tri_state"))
    )
    (net (code "56") (name "/Tube3-3") (class "Default")
      (node (ref "Q32") (pin "1") (pinfunction "B_1") (pintype "passive"))
      (node (ref "U11") (pin "2") (pinfunction "QC_2") (pintype "tri_state"))
    )
    (net (code "57") (name "/Tube3-4") (class "Default")
      (node (ref "Q31") (pin "1") (pinfunction "B_1") (pintype "passive"))
      (node (ref "U11") (pin "1") (pinfunction "QB_1") (pintype "tri_state"))
    )
    (net (code "58") (name "/Tube3-5") (class "Default")
      (node (ref "Q30") (pin "1") (pinfunction "B_1") (pintype "passive"))
      (node (ref "U11") (pin "15") (pinfunction "QA_15") (pintype "tri_state"))
    )
    (net (code "59") (name "/Tube3-6") (class "Default")
      (node (ref "Q29") (pin "1") (pinfunction "B_1") (pintype "passive"))
      (node (ref "U10") (pin "7") (pinfunction "QH_7") (pintype "tri_state"))
    )
    (net (code "60") (name "/Tube3-7") (class "Default")
      (node (ref "Q28") (pin "1") (pinfunction "B_1") (pintype "passive"))
      (node (ref "U10") (pin "6") (pinfunction "QG_6") (pintype "tri_state"))
    )
    (net (code "61") (name "/Tube3-8") (class "Default")
      (node (ref "Q27") (pin "1") (pinfunction "B_1") (pintype "passive"))
      (node (ref "U10") (pin "5") (pinfunction "QF_5") (pintype "tri_state"))
    )
    (net (code "62") (name "/Tube3-9") (class "Default")
      (node (ref "Q26") (pin "1") (pinfunction "B_1") (pintype "passive"))
      (node (ref "U10") (pin "4") (pinfunction "QE_4") (pintype "tri_state"))
    )
    (net (code "63") (name "/Tube4-0") (class "Default")
      (node (ref "Q35") (pin "1") (pinfunction "B_1") (pintype "passive"))
      (node (ref "U12") (pin "7") (pinfunction "QH_7") (pintype "tri_state"))
    )
    (net (code "64") (name "/Tube4-1") (class "Default")
      (node (ref "Q44") (pin "1") (pinfunction "B_1") (pintype "passive"))
      (node (ref "U12") (pin "6") (pinfunction "QG_6") (pintype "tri_state"))
    )
    (net (code "65") (name "/Tube4-2") (class "Default")
      (node (ref "Q43") (pin "1") (pinfunction "B_1") (pintype "passive"))
      (node (ref "U12") (pin "5") (pinfunction "QF_5") (pintype "tri_state"))
    )
    (net (code "66") (name "/Tube4-3") (class "Default")
      (node (ref "U12") (pin "4") (pinfunction "QE_4") (pintype "tri_state"))
    )
    (net (code "67") (name "/Tube4-4") (class "Default")
      (node (ref "Q41") (pin "1") (pinfunction "B_1") (pintype "passive"))
      (node (ref "U12") (pin "3") (pinfunction "QD_3") (pintype "tri_state"))
    )
    (net (code "68") (name "/Tube4-5") (class "Default")
      (node (ref "Q40") (pin "1") (pinfunction "B_1") (pintype "passive"))
      (node (ref "U12") (pin "2") (pinfunction "QC_2") (pintype "tri_state"))
    )
    (net (code "69") (name "/Tube4-6") (class "Default")
      (node (ref "Q39") (pin "1") (pinfunction "B_1") (pintype "passive"))
      (node (ref "U12") (pin "1") (pinfunction "QB_1") (pintype "tri_state"))
    )
    (net (code "70") (name "/Tube4-7") (class "Default")
      (node (ref "Q38") (pin "1") (pinfunction "B_1") (pintype "passive"))
      (node (ref "U12") (pin "15") (pinfunction "QA_15") (pintype "tri_state"))
    )
    (net (code "71") (name "/Tube4-8") (class "Default")
      (node (ref "Q37") (pin "1") (pinfunction "B_1") (pintype "passive"))
      (node (ref "U11") (pin "7") (pinfunction "QH_7") (pintype "tri_state"))
    )
    (net (code "72") (name "/Tube4-9") (class "Default")
      (node (ref "Q36") (pin "1") (pinfunction "B_1") (pintype "passive"))
      (node (ref "U11") (pin "6") (pinfunction "QG_6") (pintype "tri_state"))
    )
    (net (code "73") (name "/UD+") (class "Default")
      (node (ref "J7") (pin "3") (pinfunction "D+_3") (pintype "passive"))
      (node (ref "U13") (pin "5") (pinfunction "UD+_5") (pintype "passive"))
    )
    (net (code "74") (name "/UD-") (class "Default")
      (node (ref "J7") (pin "2") (pinfunction "D-_2") (pintype "passive"))
      (node (ref "U13") (pin "6") (pinfunction "UD-_6") (pintype "passive"))
    )
    (net (code "75") (name "3V3") (class "Default")
      (node (ref "C16") (pin "1") (pinfunction "1_1") (pintype "passive"))
      (node (ref "C17") (pin "1") (pinfunction "1_1") (pintype "passive"))
      (node (ref "C18") (pin "1") (pinfunction "1_1") (pintype "passive"))
      (node (ref "C3") (pin "2") (pinfunction "2_2") (pintype "passive"))
      (node (ref "C32") (pin "1") (pinfunction "1_1") (pintype "passive"))
      (node (ref "D2") (pin "A") (pinfunction "A_A") (pintype "passive"))
      (node (ref "J5") (pin "1") (pinfunction "1_1") (pintype "passive"))
      (node (ref "P1") (pin "2") (pinfunction "2_2") (pintype "passive"))
      (node (ref "Q46") (pin "2") (pinfunction "E_2") (pintype "passive"))
      (node (ref "R1") (pin "1") (pinfunction "1_1") (pintype "passive"))
      (node (ref "R16") (pin "1") (pinfunction "1_1") (pintype "passive"))
      (node (ref "R17") (pin "2") (pinfunction "2_2") (pintype "passive"))
      (node (ref "R20") (pin "2") (pinfunction "2_2") (pintype "passive"))
      (node (ref "R21") (pin "2") (pinfunction "2_2") (pintype "passive"))
      (node (ref "R22") (pin "2") (pinfunction "2_2") (pintype "passive"))
      (node (ref "R23") (pin "2") (pinfunction "2_2") (pintype "passive"))
      (node (ref "R25") (pin "1") (pinfunction "1_1") (pintype "passive"))
      (node (ref "R26") (pin "1") (pinfunction "1_1") (pintype "passive"))
      (node (ref "R27") (pin "1") (pinfunction "1_1") (pintype "passive"))
      (node (ref "R28") (pin "1") (pinfunction "1_1") (pintype "passive"))
      (node (ref "R29") (pin "1") (pinfunction "1_1") (pintype "passive"))
      (node (ref "R30") (pin "1") (pinfunction "1_1") (pintype "passive"))
      (node (ref "R31") (pin "1") (pinfunction "1_1") (pintype "passive"))
      (node (ref "R32") (pin "2") (pinfunction "2_2") (pintype "passive"))
      (node (ref "R34") (pin "2") (pinfunction "2_2") (pintype "passive"))
      (node (ref "U13") (pin "16") (pinfunction "VCC_16") (pintype "passive"))
      (node (ref "U14") (pin "3") (pinfunction "VDD_3") (pintype "passive"))
      (node (ref "U15") (pin "2") (pinfunction "VCC_2") (pintype "passive"))
      (node (ref "U16") (pin "3") (pinfunction "VCC_3") (pintype "passive"))
      (node (ref "U7") (pin "1") (pinfunction "VBAT_1") (pintype "power_in"))
      (node (ref "U7") (pin "13") (pinfunction "VDDA_13") (pintype "power_in"))
      (node (ref "U7") (pin "19") (pinfunction "VDD_4_19") (pintype "power_in"))
      (node (ref "U7") (pin "32") (pinfunction "VDD_1_32") (pintype "power_in"))
      (node (ref "U7") (pin "48") (pinfunction "VDD_2_48") (pintype "power_in"))
      (node (ref "U7") (pin "64") (pinfunction "VDD_3_64") (pintype "power_in"))
      (node (ref "VR1") (pin "2") (pinfunction "Vout_2") (pintype "passive"))
    )
    (net (code "76") (name "DGND") (class "Default")
      (node (ref "BT1") (pin "2") (pinfunction "-_2") (pintype "passive"))
      (node (ref "C14") (pin "1") (pinfunction "1_1") (pintype "passive"))
      (node (ref "C15") (pin "1") (pinfunction "1_1") (pintype "passive"))
      (node (ref "C16") (pin "2") (pinfunction "2_2") (pintype "passive"))
      (node (ref "C17") (pin "2") (pinfunction "2_2") (pintype "passive"))
      (node (ref "C18") (pin "2") (pinfunction "2_2") (pintype "passive"))
      (node (ref "C19") (pin "1") (pinfunction "1_1") (pintype "passive"))
      (node (ref "C20") (pin "2") (pinfunction "2_2") (pintype "passive"))
      (node (ref "C21") (pin "2") (pinfunction "2_2") (pintype "passive"))
      (node (ref "C22") (pin "2") (pinfunction "2_2") (pintype "passive"))
      (node (ref "C23") (pin "2") (pinfunction "2_2") (pintype "passive"))
      (node (ref "C24") (pin "2") (pinfunction "2_2") (pintype "passive"))
      (node (ref "C25") (pin "2") (pinfunction "2_2") (pintype "passive"))
      (node (ref "C26") (pin "2") (pinfunction "2_2") (pintype "passive"))
      (node (ref "C27") (pin "2") (pinfunction "2_2") (pintype "passive"))
      (node (ref "C28") (pin "1") (pinfunction "1_1") (pintype "passive"))
      (node (ref "C29") (pin "1") (pinfunction "1_1") (pintype "passive"))
      (node (ref "C30") (pin "1") (pinfunction "1_1") (pintype "passive"))
      (node (ref "C31") (pin "1") (pinfunction "1_1") (pintype "passive"))
      (node (ref "C32") (pin "2") (pinfunction "2_2") (pintype "passive"))
      (node (ref "C4") (pin "1") (pinfunction "1_1") (pintype "passive"))
      (node (ref "J7") (pin "4") (pinfunction "ID_4") (pintype "passive"))
      (node (ref "J7") (pin "5") (pinfunction "VSS_5") (pintype "passive"))
      (node (ref "L2") (pin "2") (pinfunction "2_2") (pintype "passive"))
      (node (ref "P1") (pin "3") (pinfunction "3_3") (pintype "passive"))
      (node (ref "P2") (pin "1") (pinfunction "1_1") (pintype "passive"))
      (node (ref "Q47") (pin "2") (pinfunction "E_2") (pintype "passive"))
      (node (ref "R12") (pin "1") (pinfunction "1_1") (pintype "passive"))
      (node (ref "R15") (pin "1") (pinfunction "1_1") (pintype "passive"))
      (node (ref "S1") (pin "2") (pinfunction "2_2") (pintype "passive"))
      (node (ref "S2") (pin "1") (pinfunction "1_1") (pintype "passive"))
      (node (ref "S3") (pin "1") (pinfunction "1_1") (pintype "passive"))
      (node (ref "S4") (pin "1") (pinfunction "1_1") (pintype "passive"))
      (node (ref "S5") (pin "1") (pinfunction "1_1") (pintype "passive"))
      (node (ref "U10") (pin "8") (pinfunction "GND_8") (pintype "power_in"))
      (node (ref "U11") (pin "8") (pinfunction "GND_8") (pintype "power_in"))
      (node (ref "U12") (pin "8") (pinfunction "GND_8") (pintype "power_in"))
      (node (ref "U13") (pin "1") (pinfunction "GND_1") (pintype "passive"))
      (node (ref "U14") (pin "1") (pinfunction "GND_1") (pintype "passive"))
      (node (ref "U15") (pin "10") (pinfunction "N.C._10") (pintype "passive"))
      (node (ref "U15") (pin "11") (pinfunction "N.C._11") (pintype "passive"))
      (node (ref "U15") (pin "12") (pinfunction "N.C._12") (pintype "passive"))
      (node (ref "U15") (pin "13") (pinfunction "GND_13") (pintype "passive"))
      (node (ref "U15") (pin "5") (pinfunction "N.C._5") (pintype "passive"))
      (node (ref "U15") (pin "6") (pinfunction "N.C._6") (pintype "passive"))
      (node (ref "U15") (pin "7") (pinfunction "N.C._7") (pintype "passive"))
      (node (ref "U15") (pin "8") (pinfunction "N.C._8") (pintype "passive"))
      (node (ref "U15") (pin "9") (pinfunction "N.C._9") (pintype "passive"))
      (node (ref "U16") (pin "2") (pinfunction "GND_2") (pintype "passive"))
      (node (ref "U7") (pin "12") (pinfunction "VSSA_12") (pintype "power_in"))
      (node (ref "U7") (pin "18") (pinfunction "VSS_4_18") (pintype "power_in"))
      (node (ref "U7") (pin "31") (pinfunction "VSS_1_31") (pintype "power_in"))
      (node (ref "U7") (pin "47") (pinfunction "VSS_2_47") (pintype "power_in"))
      (node (ref "U7") (pin "63") (pinfunction "VSS_3_63") (pintype "power_in"))
      (node (ref "U8") (pin "8") (pinfunction "GND_8") (pintype "power_in"))
      (node (ref "U9") (pin "8") (pinfunction "GND_8") (pintype "power_in"))
    )
    (net (code "77") (name "GND") (class "Default")
      (node (ref "C10") (pin "2") (pinfunction "2_2") (pintype "passive"))
      (node (ref "C11") (pin "2") (pinfunction "2_2") (pintype "passive"))
      (node (ref "C12") (pin "1") (pinfunction "1_1") (pintype "passive"))
      (node (ref "C13") (pin "2") (pinfunction "2_2") (pintype "passive"))
      (node (ref "C2") (pin "1") (pinfunction "1_1") (pintype "passive"))
      (node (ref "C3") (pin "1") (pinfunction "1_1") (pintype "passive"))
      (node (ref "C5") (pin "2") (pinfunction "2_2") (pintype "passive"))
      (node (ref "C6") (pin "2") (pinfunction "2_2") (pintype "passive"))
      (node (ref "C7") (pin "2") (pinfunction "2_2") (pintype "passive"))
      (node (ref "C8") (pin "2") (pinfunction "2_2") (pintype "passive"))
      (node (ref "C9") (pin "1") (pinfunction "1_1") (pintype "passive"))
      (node (ref "J6") (pin "1") (pinfunction "1_1") (pintype "passive"))
      (node (ref "L2") (pin "1") (pinfunction "1_1") (pintype "passive"))
      (node (ref "Q1") (pin "2") (pinfunction "E_2") (pintype "passive"))
      (node (ref "Q10") (pin "2") (pinfunction "E_2") (pintype "passive"))
      (node (ref "Q11") (pin "2") (pinfunction "E_2") (pintype "passive"))
      (node (ref "Q12") (pin "2") (pinfunction "E_2") (pintype "passive"))
      (node (ref "Q13") (pin "2") (pinfunction "E_2") (pintype "passive"))
      (node (ref "Q14") (pin "2") (pinfunction "E_2") (pintype "passive"))
      (node (ref "Q15") (pin "2") (pinfunction "E_2") (pintype "passive"))
      (node (ref "Q16") (pin "2") (pinfunction "E_2") (pintype "passive"))
      (node (ref "Q17") (pin "2") (pinfunction "E_2") (pintype "passive"))
      (node (ref "Q18") (pin "2") (pinfunction "E_2") (pintype "passive"))
      (node (ref "Q19") (pin "2") (pinfunction "E_2") (pintype "passive"))
      (node (ref "Q20") (pin "2") (pinfunction "E_2") (pintype "passive"))
      (node (ref "Q21") (pin "2") (pinfunction "E_2") (pintype "passive"))
      (node (ref "Q22") (pin "2") (pinfunction "E_2") (pintype "passive"))
      (node (ref "Q23") (pin "2") (pinfunction "E_2") (pintype "passive"))
      (node (ref "Q24") (pin "2") (pinfunction "E_2") (pintype "passive"))
      (node (ref "Q25") (pin "2") (pinfunction "E_2") (pintype "passive"))
      (node (ref "Q26") (pin "2") (pinfunction "E_2") (pintype "passive"))
      (node (ref "Q27") (pin "2") (pinfunction "E_2") (pintype "passive"))
      (node (ref "Q28") (pin "2") (pinfunction "E_2") (pintype "passive"))
      (node (ref "Q29") (pin "2") (pinfunction "E_2") (pintype "passive"))
      (node (ref "Q3") (pin "2") (pinfunction "E_2") (pintype "passive"))
      (node (ref "Q30") (pin "2") (pinfunction "E_2") (pintype "passive"))
      (node (ref "Q31") (pin "2") (pinfunction "E_2") (pintype "passive"))
      (node (ref "Q32") (pin "2") (pinfunction "E_2") (pintype "passive"))
      (node (ref "Q33") (pin "2") (pinfunction "E_2") (pintype "passive"))
      (node (ref "Q34") (pin "2") (pinfunction "E_2") (pintype "passive"))
      (node (ref "Q35") (pin "2") (pinfunction "E_2") (pintype "passive"))
      (node (ref "Q36") (pin "2") (pinfunction "E_2") (pintype "passive"))
      (node (ref "Q37") (pin "2") (pinfunction "E_2") (pintype "passive"))
      (node (ref "Q38") (pin "2") (pinfunction "E_2") (pintype "passive"))
      (node (ref "Q39") (pin "2") (pinfunction "E_2") (pintype "passive"))
      (node (ref "Q4") (pin "3") (pinfunction "S_3") (pintype "passive"))
      (node (ref "Q40") (pin "2") (pinfunction "E_2") (pintype "passive"))
      (node (ref "Q41") (pin "2") (pinfunction "E_2") (pintype "passive"))
      (node (ref "Q42") (pin "2") (pinfunction "E_2") (pintype "passive"))
      (node (ref "Q43") (pin "2") (pinfunction "E_2") (pintype "passive"))
      (node (ref "Q44") (pin "2") (pinfunction "E_2") (pintype "passive"))
      (node (ref "Q5") (pin "2") (pinfunction "E_2") (pintype "passive"))
      (node (ref "Q6") (pin "2") (pinfunction "E_2") (pintype "passive"))
      (node (ref "Q7") (pin "2") (pinfunction "E_2") (pintype "passive"))
      (node (ref "Q8") (pin "2") (pinfunction "E_2") (pintype "passive"))
      (node (ref "Q9") (pin "2") (pinfunction "E_2") (pintype "passive"))
      (node (ref "R3") (pin "1") (pinfunction "1_1") (pintype "passive"))
      (node (ref "R9") (pin "1") (pinfunction "1_1") (pintype "passive"))
      (node (ref "U1") (pin "4") (pinfunction "OUT-_4") (pintype "passive"))
      (node (ref "U2") (pin "3") (pinfunction "VSS_3") (pintype "passive"))
      (node (ref "U3") (pin "3") (pinfunction "VSS_3") (pintype "passive"))
      (node (ref "U4") (pin "3") (pinfunction "VSS_3") (pintype "passive"))
      (node (ref "U5") (pin "3") (pinfunction "VSS_3") (pintype "passive"))
      (node (ref "U6") (pin "4") (pinfunction "GND_4") (pintype "passive"))
      (node (ref "VR1") (pin "1") (pinfunction "GND_1") (pintype "passive"))
    )
    (net (code "78") (name "Net-(*1-Anode)") (class "Default")
      (node (ref "*1") (pin "2") (pinfunction "Anode_2") (pintype "passive"))
      (node (ref "R6") (pin "1") (pinfunction "1_1") (pintype "passive"))
    )
    (net (code "79") (name "Net-(*1-K'0')") (class "Default")
      (node (ref "*1") (pin "3") (pinfunction "K'0'_3") (pintype "passive"))
      (node (ref "Q15") (pin "3") (pinfunction "C_3") (pintype "passive"))
    )
    (net (code "80") (name "Net-(*1-K'1')") (class "Default")
      (node (ref "*1") (pin "13") (pinfunction "K'1'_13") (pintype "passive"))
      (node (ref "Q24") (pin "3") (pinfunction "C_3") (pintype "passive"))
    )
    (net (code "81") (name "Net-(*1-K'2')") (class "Default")
      (node (ref "*1") (pin "12") (pinfunction "K'2'_12") (pintype "passive"))
      (node (ref "Q23") (pin "3") (pinfunction "C_3") (pintype "passive"))
    )
    (net (code "82") (name "Net-(*1-K'3')") (class "Default")
      (node (ref "*1") (pin "11") (pinfunction "K'3'_11") (pintype "passive"))
      (node (ref "Q22") (pin "3") (pinfunction "C_3") (pintype "passive"))
    )
    (net (code "83") (name "Net-(*1-K'4')") (class "Default")
      (node (ref "*1") (pin "10") (pinfunction "K'4'_10") (pintype "passive"))
      (node (ref "Q21") (pin "3") (pinfunction "C_3") (pintype "passive"))
    )
    (net (code "84") (name "Net-(*1-K'5')") (class "Default")
      (node (ref "*1") (pin "9") (pinfunction "K'5'_9") (pintype "passive"))
      (node (ref "Q20") (pin "3") (pinfunction "C_3") (pintype "passive"))
    )
    (net (code "85") (name "Net-(*1-K'6')") (class "Default")
      (node (ref "*1") (pin "7") (pinfunction "K'6'_7") (pintype "passive"))
      (node (ref "Q19") (pin "3") (pinfunction "C_3") (pintype "passive"))
    )
    (net (code "86") (name "Net-(*1-K'7')") (class "Default")
      (node (ref "*1") (pin "6") (pinfunction "K'7'_6") (pintype "passive"))
      (node (ref "Q18") (pin "3") (pinfunction "C_3") (pintype "passive"))
    )
    (net (code "87") (name "Net-(*1-K'8')") (class "Default")
      (node (ref "*1") (pin "5") (pinfunction "K'8'_5") (pintype "passive"))
      (node (ref "Q17") (pin "3") (pinfunction "C_3") (pintype "passive"))
    )
    (net (code "88") (name "Net-(*1-K'9')") (class "Default")
      (node (ref "*1") (pin "4") (pinfunction "K'9'_4") (pintype "passive"))
      (node (ref "Q16") (pin "3") (pinfunction "C_3") (pintype "passive"))
    )
    (net (code "89") (name "Net-(*2-Anode)") (class "Default")
      (node (ref "*2") (pin "2") (pinfunction "Anode_2") (pintype "passive"))
      (node (ref "R7") (pin "1") (pinfunction "1_1") (pintype "passive"))
    )
    (net (code "90") (name "Net-(*2-K'0')") (class "Default")
      (node (ref "*2") (pin "3") (pinfunction "K'0'_3") (pintype "passive"))
      (node (ref "Q5") (pin "3") (pinfunction "C_3") (pintype "passive"))
    )
    (net (code "91") (name "Net-(*2-K'1')") (class "Default")
      (node (ref "*2") (pin "13") (pinfunction "K'1'_13") (pintype "passive"))
      (node (ref "Q14") (pin "3") (pinfunction "C_3") (pintype "passive"))
    )
    (net (code "92") (name "Net-(*2-K'2')") (class "Default")
      (node (ref "*2") (pin "12") (pinfunction "K'2'_12") (pintype "passive"))
      (node (ref "Q13") (pin "3") (pinfunction "C_3") (pintype "passive"))
    )
    (net (code "93") (name "Net-(*2-K'3')") (class "Default")
      (node (ref "*2") (pin "11") (pinfunction "K'3'_11") (pintype "passive"))
      (node (ref "Q12") (pin "3") (pinfunction "C_3") (pintype "passive"))
    )
    (net (code "94") (name "Net-(*2-K'4')") (class "Default")
      (node (ref "*2") (pin "10") (pinfunction "K'4'_10") (pintype "passive"))
      (node (ref "Q11") (pin "3") (pinfunction "C_3") (pintype "passive"))
    )
    (net (code "95") (name "Net-(*2-K'5')") (class "Default")
      (node (ref "*2") (pin "9") (pinfunction "K'5'_9") (pintype "passive"))
      (node (ref "Q10") (pin "3") (pinfunction "C_3") (pintype "passive"))
    )
    (net (code "96") (name "Net-(*2-K'6')") (class "Default")
      (node (ref "*2") (pin "7") (pinfunction "K'6'_7") (pintype "passive"))
      (node (ref "Q9") (pin "3") (pinfunction "C_3") (pintype "passive"))
    )
    (net (code "97") (name "Net-(*2-K'7')") (class "Default")
      (node (ref "*2") (pin "6") (pinfunction "K'7'_6") (pintype "passive"))
      (node (ref "Q8") (pin "3") (pinfunction "C_3") (pintype "passive"))
    )
    (net (code "98") (name "Net-(*2-K'8')") (class "Default")
      (node (ref "*2") (pin "5") (pinfunction "K'8'_5") (pintype "passive"))
      (node (ref "Q7") (pin "3") (pinfunction "C_3") (pintype "passive"))
    )
    (net (code "99") (name "Net-(*2-K'9')") (class "Default")
      (node (ref "*2") (pin "4") (pinfunction "K'9'_4") (pintype "passive"))
      (node (ref "Q6") (pin "3") (pinfunction "C_3") (pintype "passive"))
    )
    (net (code "100") (name "Net-(*3-Anode)") (class "Default")
      (node (ref "*3") (pin "2") (pinfunction "Anode_2") (pintype "passive"))
      (node (ref "R13") (pin "1") (pinfunction "1_1") (pintype "passive"))
    )
    (net (code "101") (name "Net-(*3-K'0')") (class "Default")
      (node (ref "*3") (pin "3") (pinfunction "K'0'_3") (pintype "passive"))
      (node (ref "Q35") (pin "3") (pinfunction "C_3") (pintype "passive"))
    )
    (net (code "102") (name "Net-(*3-K'1')") (class "Default")
      (node (ref "*3") (pin "13") (pinfunction "K'1'_13") (pintype "passive"))
      (node (ref "Q44") (pin "3") (pinfunction "C_3") (pintype "passive"))
    )
    (net (code "103") (name "Net-(*3-K'2')") (class "Default")
      (node (ref "*3") (pin "12") (pinfunction "K'2'_12") (pintype "passive"))
      (node (ref "Q43") (pin "3") (pinfunction "C_3") (pintype "passive"))
    )
    (net (code "104") (name "Net-(*3-K'3')") (class "Default")
      (node (ref "*3") (pin "11") (pinfunction "K'3'_11") (pintype "passive"))
      (node (ref "Q42") (pin "3") (pinfunction "C_3") (pintype "passive"))
    )
    (net (code "105") (name "Net-(*3-K'4')") (class "Default")
      (node (ref "*3") (pin "10") (pinfunction "K'4'_10") (pintype "passive"))
      (node (ref "Q41") (pin "3") (pinfunction "C_3") (pintype "passive"))
    )
    (net (code "106") (name "Net-(*3-K'5')") (class "Default")
      (node (ref "*3") (pin "9") (pinfunction "K'5'_9") (pintype "passive"))
      (node (ref "Q40") (pin "3") (pinfunction "C_3") (pintype "passive"))
    )
    (net (code "107") (name "Net-(*3-K'6')") (class "Default")
      (node (ref "*3") (pin "7") (pinfunction "K'6'_7") (pintype "passive"))
      (node (ref "Q39") (pin "3") (pinfunction "C_3") (pintype "passive"))
    )
    (net (code "108") (name "Net-(*3-K'7')") (class "Default")
      (node (ref "*3") (pin "6") (pinfunction "K'7'_6") (pintype "passive"))
      (node (ref "Q38") (pin "3") (pinfunction "C_3") (pintype "passive"))
    )
    (net (code "109") (name "Net-(*3-K'8')") (class "Default")
      (node (ref "*3") (pin "5") (pinfunction "K'8'_5") (pintype "passive"))
      (node (ref "Q37") (pin "3") (pinfunction "C_3") (pintype "passive"))
    )
    (net (code "110") (name "Net-(*3-K'9')") (class "Default")
      (node (ref "*3") (pin "4") (pinfunction "K'9'_4") (pintype "passive"))
      (node (ref "Q36") (pin "3") (pinfunction "C_3") (pintype "passive"))
    )
    (net (code "111") (name "Net-(*4-Anode)") (class "Default")
      (node (ref "*4") (pin "2") (pinfunction "Anode_2") (pintype "passive"))
      (node (ref "R14") (pin "1") (pinfunction "1_1") (pintype "passive"))
    )
    (net (code "112") (name "Net-(*4-K'0')") (class "Default")
      (node (ref "*4") (pin "3") (pinfunction "K'0'_3") (pintype "passive"))
      (node (ref "Q25") (pin "3") (pinfunction "C_3") (pintype "passive"))
    )
    (net (code "113") (name "Net-(*4-K'1')") (class "Default")
      (node (ref "*4") (pin "13") (pinfunction "K'1'_13") (pintype "passive"))
      (node (ref "Q34") (pin "3") (pinfunction "C_3") (pintype "passive"))
    )
    (net (code "114") (name "Net-(*4-K'2')") (class "Default")
      (node (ref "*4") (pin "12") (pinfunction "K'2'_12") (pintype "passive"))
      (node (ref "Q33") (pin "3") (pinfunction "C_3") (pintype "passive"))
    )
    (net (code "115") (name "Net-(*4-K'3')") (class "Default")
      (node (ref "*4") (pin "11") (pinfunction "K'3'_11") (pintype "passive"))
      (node (ref "Q32") (pin "3") (pinfunction "C_3") (pintype "passive"))
    )
    (net (code "116") (name "Net-(*4-K'4')") (class "Default")
      (node (ref "*4") (pin "10") (pinfunction "K'4'_10") (pintype "passive"))
      (node (ref "Q31") (pin "3") (pinfunction "C_3") (pintype "passive"))
    )
    (net (code "117") (name "Net-(*4-K'5')") (class "Default")
      (node (ref "*4") (pin "9") (pinfunction "K'5'_9") (pintype "passive"))
      (node (ref "Q30") (pin "3") (pinfunction "C_3") (pintype "passive"))
    )
    (net (code "118") (name "Net-(*4-K'6')") (class "Default")
      (node (ref "*4") (pin "7") (pinfunction "K'6'_7") (pintype "passive"))
      (node (ref "Q29") (pin "3") (pinfunction "C_3") (pintype "passive"))
    )
    (net (code "119") (name "Net-(*4-K'7')") (class "Default")
      (node (ref "*4") (pin "6") (pinfunction "K'7'_6") (pintype "passive"))
      (node (ref "Q28") (pin "3") (pinfunction "C_3") (pintype "passive"))
    )
    (net (code "120") (name "Net-(*4-K'8')") (class "Default")
      (node (ref "*4") (pin "5") (pinfunction "K'8'_5") (pintype "passive"))
      (node (ref "Q27") (pin "3") (pinfunction "C_3") (pintype "passive"))
    )
    (net (code "121") (name "Net-(*4-K'9')") (class "Default")
      (node (ref "*4") (pin "4") (pinfunction "K'9'_4") (pintype "passive"))
      (node (ref "Q26") (pin "3") (pinfunction "C_3") (pintype "passive"))
    )
    (net (code "122") (name "Net-(BT1-+)") (class "Default")
      (node (ref "BT1") (pin "1") (pinfunction "+_1") (pintype "passive"))
      (node (ref "U15") (pin "14") (pinfunction "VBAT_14") (pintype "passive"))
    )
    (net (code "123") (name "Net-(D1-A)") (class "Default")
      (node (ref "D1") (pin "1") (pinfunction "A_1") (pintype "passive"))
      (node (ref "L1") (pin "2") (pinfunction "2_2") (pintype "passive"))
      (node (ref "Q4") (pin "2") (pinfunction "D_2") (pintype "passive"))
    )
    (net (code "124") (name "Net-(D2-PadK)") (class "Default")
      (node (ref "D2") (pin "K") (pinfunction "K_K") (pintype "passive"))
      (node (ref "R11") (pin "1") (pinfunction "1_1") (pintype "passive"))
    )
    (net (code "125") (name "Net-(D3-K)") (class "Default")
      (node (ref "D3") (pin "2") (pinfunction "K_2") (pintype "passive"))
      (node (ref "Q45") (pin "3") (pinfunction "C_3") (pintype "passive"))
      (node (ref "R17") (pin "1") (pinfunction "1_1") (pintype "passive"))
    )
    (net (code "126") (name "Net-(J8-1)") (class "Default")
      (node (ref "J8") (pin "2") (pinfunction "1_2") (pintype "passive"))
      (node (ref "Q47") (pin "3") (pinfunction "C_3") (pintype "passive"))
    )
    (net (code "127") (name "Net-(Q1-B)") (class "Default")
      (node (ref "Q1") (pin "1") (pinfunction "B_1") (pintype "passive"))
      (node (ref "R2") (pin "2") (pinfunction "2_2") (pintype "passive"))
    )
    (net (code "128") (name "Net-(Q1-C)") (class "Default")
      (node (ref "Q1") (pin "3") (pinfunction "C_3") (pintype "passive"))
      (node (ref "UP1") (pin "2") (pinfunction "2_2") (pintype "passive"))
    )
    (net (code "129") (name "Net-(Q2-E)") (class "Default")
      (node (ref "C12") (pin "2") (pinfunction "2_2") (pintype "passive"))
      (node (ref "C13") (pin "1") (pinfunction "1_1") (pintype "passive"))
      (node (ref "L1") (pin "1") (pinfunction "1_1") (pintype "passive"))
      (node (ref "Q2") (pin "2") (pinfunction "E_2") (pintype "passive"))
      (node (ref "U6") (pin "1") (pinfunction "SC_1") (pintype "passive"))
      (node (ref "U6") (pin "6") (pinfunction "VCC_6") (pintype "passive"))
      (node (ref "U6") (pin "7") (pinfunction "IPK_7") (pintype "passive"))
      (node (ref "U6") (pin "8") (pinfunction "DRI_8") (pintype "passive"))
    )
    (net (code "130") (name "Net-(Q3-B)") (class "Default")
      (node (ref "Q3") (pin "1") (pinfunction "B_1") (pintype "passive"))
      (node (ref "R8") (pin "1") (pinfunction "1_1") (pintype "passive"))
    )
    (net (code "131") (name "Net-(Q3-C)") (class "Default")
      (node (ref "Q3") (pin "3") (pinfunction "C_3") (pintype "passive"))
      (node (ref "UP2") (pin "2") (pinfunction "2_2") (pintype "passive"))
    )
    (net (code "132") (name "Net-(Q4-G)") (class "Default")
      (node (ref "Q4") (pin "1") (pinfunction "G_1") (pintype "passive"))
      (node (ref "R9") (pin "2") (pinfunction "2_2") (pintype "passive"))
      (node (ref "U6") (pin "2") (pinfunction "SE_2") (pintype "passive"))
    )
    (net (code "133") (name "Net-(Q45-B)") (class "Default")
      (node (ref "Q45") (pin "1") (pinfunction "B_1") (pintype "passive"))
      (node (ref "R18") (pin "2") (pinfunction "2_2") (pintype "passive"))
    )
    (net (code "134") (name "Net-(Q45-E)") (class "Default")
      (node (ref "Q45") (pin "2") (pinfunction "E_2") (pintype "passive"))
      (node (ref "R19") (pin "1") (pinfunction "1_1") (pintype "passive"))
      (node (ref "U13") (pin "11") (pinfunction "RTS#_11") (pintype "passive"))
    )
    (net (code "135") (name "Net-(Q46-B)") (class "Default")
      (node (ref "Q46") (pin "1") (pinfunction "B_1") (pintype "passive"))
      (node (ref "R19") (pin "2") (pinfunction "2_2") (pintype "passive"))
    )
    (net (code "136") (name "Net-(Q46-C)") (class "Default")
      (node (ref "Q46") (pin "3") (pinfunction "C_3") (pintype "passive"))
      (node (ref "R24") (pin "2") (pinfunction "2_2") (pintype "passive"))
    )
    (net (code "137") (name "Net-(Q47-B)") (class "Default")
      (node (ref "Q47") (pin "1") (pinfunction "B_1") (pintype "passive"))
      (node (ref "R33") (pin "2") (pinfunction "2_2") (pintype "passive"))
    )
    (net (code "138") (name "Net-(R5-Pad1)") (class "Default")
      (node (ref "R5") (pin "1") (pinfunction "1_1") (pintype "passive"))
      (node (ref "UP1") (pin "1") (pinfunction "1_1") (pintype "passive"))
    )
    (net (code "139") (name "Net-(R10-Pad1)") (class "Default")
      (node (ref "R10") (pin "1") (pinfunction "1_1") (pintype "passive"))
      (node (ref "UP2") (pin "1") (pinfunction "1_1") (pintype "passive"))
    )
    (net (code "140") (name "Net-(U1-IN-)") (class "Default")
      (node (ref "C1") (pin "2") (pinfunction "2_2") (pintype "passive"))
      (node (ref "J1") (pin "2") (pinfunction "2_2") (pintype "power_in"))
      (node (ref "J1") (pin "3") (pinfunction "3_3") (pintype "power_in"))
      (node (ref "U1") (pin "1") (pinfunction "IN-_1") (pintype "passive"))
    )
    (net (code "141") (name "Net-(U2-DO)") (class "Default")
      (node (ref "U2") (pin "2") (pinfunction "DO_2") (pintype "passive"))
      (node (ref "U3") (pin "4") (pinfunction "DI_4") (pintype "passive"))
    )
    (net (code "142") (name "Net-(U3-DO)") (class "Default")
      (node (ref "U3") (pin "2") (pinfunction "DO_2") (pintype "passive"))
      (node (ref "U4") (pin "4") (pinfunction "DI_4") (pintype "passive"))
    )
    (net (code "143") (name "Net-(U4-DO)") (class "Default")
      (node (ref "U4") (pin "2") (pinfunction "DO_2") (pintype "passive"))
      (node (ref "U5") (pin "4") (pinfunction "DI_4") (pintype "passive"))
    )
    (net (code "144") (name "Net-(U6-FB)") (class "Default")
      (node (ref "C9") (pin "2") (pinfunction "2_2") (pintype "passive"))
      (node (ref "R3") (pin "2") (pinfunction "2_2") (pintype "passive"))
      (node (ref "R4") (pin "1") (pinfunction "1_1") (pintype "passive"))
      (node (ref "U6") (pin "5") (pinfunction "FB_5") (pintype "passive"))
    )
    (net (code "145") (name "Net-(U6-TC)") (class "Default")
      (node (ref "C10") (pin "1") (pinfunction "1_1") (pintype "passive"))
      (node (ref "U6") (pin "3") (pinfunction "TC_3") (pintype "passive"))
    )
    (net (code "146") (name "Net-(U7A-PD0-OSC_IN)") (class "Default")
      (node (ref "C14") (pin "2") (pinfunction "2_2") (pintype "passive"))
      (node (ref "U7") (pin "5") (pinfunction "PD0-OSC_IN_5") (pintype "bidirectional"))
      (node (ref "Y1") (pin "1") (pinfunction "OSC1_1") (pintype "passive"))
    )
    (net (code "147") (name "Net-(U7A-PD1)") (class "Default")
      (node (ref "C15") (pin "2") (pinfunction "2_2") (pintype "passive"))
      (node (ref "U7") (pin "6") (pinfunction "PD1_6") (pintype "bidirectional"))
      (node (ref "Y1") (pin "2") (pinfunction "OSC2_2") (pintype "passive"))
    )
    (net (code "148") (name "Net-(U8-QH')") (class "Default")
      (node (ref "U8") (pin "9") (pinfunction "QH'_9") (pintype "output"))
      (node (ref "U9") (pin "14") (pinfunction "SER_14") (pintype "input"))
    )
    (net (code "149") (name "Net-(U10-QH')") (class "Default")
      (node (ref "U10") (pin "9") (pinfunction "QH'_9") (pintype "output"))
      (node (ref "U11") (pin "14") (pinfunction "SER_14") (pintype "input"))
    )
    (net (code "150") (name "Net-(U10-SER)") (class "Default")
      (node (ref "U10") (pin "14") (pinfunction "SER_14") (pintype "input"))
      (node (ref "U9") (pin "9") (pinfunction "QH'_9") (pintype "output"))
    )
    (net (code "151") (name "Net-(U11-QH')") (class "Default")
      (node (ref "U11") (pin "9") (pinfunction "QH'_9") (pintype "output"))
      (node (ref "U12") (pin "14") (pinfunction "SER_14") (pintype "input"))
    )
    (net (code "152") (name "Net-(U13-DTR#)") (class "Default")
      (node (ref "R18") (pin "1") (pinfunction "1_1") (pintype "passive"))
      (node (ref "U13") (pin "12") (pinfunction "DTR#_12") (pintype "passive"))
    )
    (net (code "153") (name "Net-(U13-V3.3)") (class "Default")
      (node (ref "C25") (pin "1") (pinfunction "1_1") (pintype "passive"))
      (node (ref "U13") (pin "4") (pinfunction "V3.3_4") (pintype "passive"))
    )
    (net (code "154") (name "Net-(U13-XI)") (class "Default")
      (node (ref "C26") (pin "1") (pinfunction "1_1") (pintype "passive"))
      (node (ref "U13") (pin "7") (pinfunction "XI_7") (pintype "passive"))
      (node (ref "Y2") (pin "1") (pinfunction "OSC1_1") (pintype "passive"))
    )
    (net (code "155") (name "Net-(U13-XO)") (class "Default")
      (node (ref "C27") (pin "1") (pinfunction "1_1") (pintype "passive"))
      (node (ref "U13") (pin "8") (pinfunction "XO_8") (pintype "passive"))
      (node (ref "Y2") (pin "2") (pinfunction "OSC2_2") (pintype "passive"))
    )
    (net (code "156") (name "VH") (class "Default")
      (node (ref "C11") (pin "1") (pinfunction "1_1") (pintype "passive"))
      (node (ref "D1") (pin "2") (pinfunction "K_2") (pintype "passive"))
      (node (ref "J2") (pin "1") (pinfunction "1_1") (pintype "passive"))
      (node (ref "R10") (pin "2") (pinfunction "2_2") (pintype "passive"))
      (node (ref "R13") (pin "2") (pinfunction "2_2") (pintype "passive"))
      (node (ref "R14") (pin "2") (pinfunction "2_2") (pintype "passive"))
      (node (ref "R4") (pin "2") (pinfunction "2_2") (pintype "passive"))
      (node (ref "R5") (pin "2") (pinfunction "2_2") (pintype "passive"))
      (node (ref "R6") (pin "2") (pinfunction "2_2") (pintype "passive"))
      (node (ref "R7") (pin "2") (pinfunction "2_2") (pintype "passive"))
    )
    (net (code "157") (name "unconnected-(*1-NC-Pad1)") (class "Default")
      (node (ref "*1") (pin "1") (pinfunction "NC_1") (pintype "passive"))
    )
    (net (code "158") (name "unconnected-(*1-NC-Pad8)") (class "Default")
      (node (ref "*1") (pin "8") (pinfunction "NC_8") (pintype "passive"))
    )
    (net (code "159") (name "unconnected-(*2-NC-Pad1)") (class "Default")
      (node (ref "*2") (pin "1") (pinfunction "NC_1") (pintype "passive"))
    )
    (net (code "160") (name "unconnected-(*2-NC-Pad8)") (class "Default")
      (node (ref "*2") (pin "8") (pinfunction "NC_8") (pintype "passive"))
    )
    (net (code "161") (name "unconnected-(*3-NC-Pad1)") (class "Default")
      (node (ref "*3") (pin "1") (pinfunction "NC_1") (pintype "passive"))
    )
    (net (code "162") (name "unconnected-(*3-NC-Pad8)") (class "Default")
      (node (ref "*3") (pin "8") (pinfunction "NC_8") (pintype "passive"))
    )
    (net (code "163") (name "unconnected-(*4-NC-Pad1)") (class "Default")
      (node (ref "*4") (pin "1") (pinfunction "NC_1") (pintype "passive"))
    )
    (net (code "164") (name "unconnected-(*4-NC-Pad8)") (class "Default")
      (node (ref "*4") (pin "8") (pinfunction "NC_8") (pintype "passive"))
    )
    (net (code "165") (name "unconnected-(Q34-B-Pad1)") (class "Default")
      (node (ref "Q34") (pin "1") (pinfunction "B_1") (pintype "passive"))
    )
    (net (code "166") (name "unconnected-(Q42-B-Pad1)") (class "Default")
      (node (ref "Q42") (pin "1") (pinfunction "B_1") (pintype "passive"))
    )
    (net (code "167") (name "unconnected-(T1-Pad1)") (class "Default")
      (node (ref "T1") (pin "1") (pinfunction "1_1") (pintype "passive"))
    )
    (net (code "168") (name "unconnected-(T2-Pad1)") (class "Default")
      (node (ref "T2") (pin "1") (pinfunction "1_1") (pintype "passive"))
    )
    (net (code "169") (name "unconnected-(T3-Pad1)") (class "Default")
      (node (ref "T3") (pin "1") (pinfunction "1_1") (pintype "passive"))
    )
    (net (code "170") (name "unconnected-(T4-Pad1)") (class "Default")
      (node (ref "T4") (pin "1") (pinfunction "1_1") (pintype "passive"))
    )
    (net (code "171") (name "unconnected-(U5-DO-Pad2)") (class "Default")
      (node (ref "U5") (pin "2") (pinfunction "DO_2") (pintype "passive"))
    )
    (net (code "172") (name "unconnected-(U7A-PA0-WKUP-Pad14)") (class "Default")
      (node (ref "U7") (pin "14") (pinfunction "PA0-WKUP_14") (pintype "bidirectional"))
    )
    (net (code "173") (name "unconnected-(U7A-PA3-Pad17)") (class "Default")
      (node (ref "U7") (pin "17") (pinfunction "PA3_17") (pintype "bidirectional"))
    )
    (net (code "174") (name "unconnected-(U7A-PA4-Pad20)") (class "Default")
      (node (ref "U7") (pin "20") (pinfunction "PA4_20") (pintype "bidirectional"))
    )
    (net (code "175") (name "unconnected-(U7A-PA5-Pad21)") (class "Default")
      (node (ref "U7") (pin "21") (pinfunction "PA5_21") (pintype "bidirectional"))
    )
    (net (code "176") (name "unconnected-(U7A-PA8-Pad41)") (class "Default")
      (node (ref "U7") (pin "41") (pinfunction "PA8_41") (pintype "bidirectional"))
    )
    (net (code "177") (name "unconnected-(U7A-PA11-Pad44)") (class "Default")
      (node (ref "U7") (pin "44") (pinfunction "PA11_44") (pintype "bidirectional"))
    )
    (net (code "178") (name "unconnected-(U7A-PA12-Pad45)") (class "Default")
      (node (ref "U7") (pin "45") (pinfunction "PA12_45") (pintype "bidirectional"))
    )
    (net (code "179") (name "unconnected-(U7A-PA15-Pad50)") (class "Default")
      (node (ref "U7") (pin "50") (pinfunction "PA15_50") (pintype "bidirectional"))
    )
    (net (code "180") (name "unconnected-(U7A-PB1-Pad27)") (class "Default")
      (node (ref "U7") (pin "27") (pinfunction "PB1_27") (pintype "bidirectional"))
    )
    (net (code "181") (name "unconnected-(U7A-PB5-Pad57)") (class "Default")
      (node (ref "U7") (pin "57") (pinfunction "PB5_57") (pintype "bidirectional"))
    )
    (net (code "182") (name "unconnected-(U7A-PB6-Pad58)") (class "Default")
      (node (ref "U7") (pin "58") (pinfunction "PB6_58") (pintype "bidirectional"))
    )
    (net (code "183") (name "unconnected-(U7A-PB7-Pad59)") (class "Default")
      (node (ref "U7") (pin "59") (pinfunction "PB7_59") (pintype "bidirectional"))
    )
    (net (code "184") (name "unconnected-(U7A-PB10-Pad29)") (class "Default")
      (node (ref "U7") (pin "29") (pinfunction "PB10_29") (pintype "bidirectional"))
    )
    (net (code "185") (name "unconnected-(U7A-PB11-Pad30)") (class "Default")
      (node (ref "U7") (pin "30") (pinfunction "PB11_30") (pintype "bidirectional"))
    )
    (net (code "186") (name "unconnected-(U7A-PB12-Pad33)") (class "Default")
      (node (ref "U7") (pin "33") (pinfunction "PB12_33") (pintype "bidirectional"))
    )
    (net (code "187") (name "unconnected-(U7A-PB13-Pad34)") (class "Default")
      (node (ref "U7") (pin "34") (pinfunction "PB13_34") (pintype "bidirectional"))
    )
    (net (code "188") (name "unconnected-(U7A-PB14-Pad35)") (class "Default")
      (node (ref "U7") (pin "35") (pinfunction "PB14_35") (pintype "bidirectional"))
    )
    (net (code "189") (name "unconnected-(U7A-PC4-Pad24)") (class "Default")
      (node (ref "U7") (pin "24") (pinfunction "PC4_24") (pintype "bidirectional"))
    )
    (net (code "190") (name "unconnected-(U7A-PC5-Pad25)") (class "Default")
      (node (ref "U7") (pin "25") (pinfunction "PC5_25") (pintype "bidirectional"))
    )
    (net (code "191") (name "unconnected-(U7A-PC6-Pad37)") (class "Default")
      (node (ref "U7") (pin "37") (pinfunction "PC6_37") (pintype "bidirectional"))
    )
    (net (code "192") (name "unconnected-(U7A-PC7-Pad38)") (class "Default")
      (node (ref "U7") (pin "38") (pinfunction "PC7_38") (pintype "bidirectional"))
    )
    (net (code "193") (name "unconnected-(U7A-PC12-Pad53)") (class "Default")
      (node (ref "U7") (pin "53") (pinfunction "PC12_53") (pintype "bidirectional"))
    )
    (net (code "194") (name "unconnected-(U7A-PC13-TAMPER-RTC-Pad2)") (class "Default")
      (node (ref "U7") (pin "2") (pinfunction "PC13-TAMPER-RTC_2") (pintype "bidirectional"))
    )
    (net (code "195") (name "unconnected-(U7A-PC14-OSC32_IN-Pad3)") (class "Default")
      (node (ref "U7") (pin "3") (pinfunction "PC14-OSC32_IN_3") (pintype "bidirectional"))
    )
    (net (code "196") (name "unconnected-(U7A-PC15-OSC32_OUT-Pad4)") (class "Default")
      (node (ref "U7") (pin "4") (pinfunction "PC15-OSC32_OUT_4") (pintype "bidirectional"))
    )
    (net (code "197") (name "unconnected-(U7A-PD2-Pad54)") (class "Default")
      (node (ref "U7") (pin "54") (pinfunction "PD2_54") (pintype "bidirectional"))
    )
    (net (code "198") (name "unconnected-(U12-QH'-Pad9)") (class "Default")
      (node (ref "U12") (pin "9") (pinfunction "QH'_9") (pintype "output"))
    )
    (net (code "199") (name "unconnected-(U13-CTS#-Pad9)") (class "Default")
      (node (ref "U13") (pin "9") (pinfunction "CTS#_9") (pintype "passive"))
    )
    (net (code "200") (name "unconnected-(U13-DCD#-Pad13)") (class "Default")
      (node (ref "U13") (pin "13") (pinfunction "DCD#_13") (pintype "passive"))
    )
    (net (code "201") (name "unconnected-(U13-DSR#-Pad15)") (class "Default")
      (node (ref "U13") (pin "15") (pinfunction "DSR#_15") (pintype "passive"))
    )
    (net (code "202") (name "unconnected-(U13-R232-Pad10)") (class "Default")
      (node (ref "U13") (pin "10") (pinfunction "R232_10") (pintype "passive"))
    )
    (net (code "203") (name "unconnected-(U13-RI#-Pad14)") (class "Default")
      (node (ref "U13") (pin "14") (pinfunction "RI#_14") (pintype "passive"))
    )
    (net (code "204") (name "unconnected-(U15-32KHZ-Pad1)") (class "Default")
      (node (ref "U15") (pin "1") (pinfunction "32KHZ_1") (pintype "passive"))
    )
    (net (code "205") (name "unconnected-(U15-~{RST}-Pad4)") (class "Default")
      (node (ref "U15") (pin "4") (pinfunction "~{RST}_4") (pintype "passive"))
    )
  )
)
